# 03_-_28PINS_SCHEMATIC.net
KiCad netlist of a schematic drawn in Altium Designer
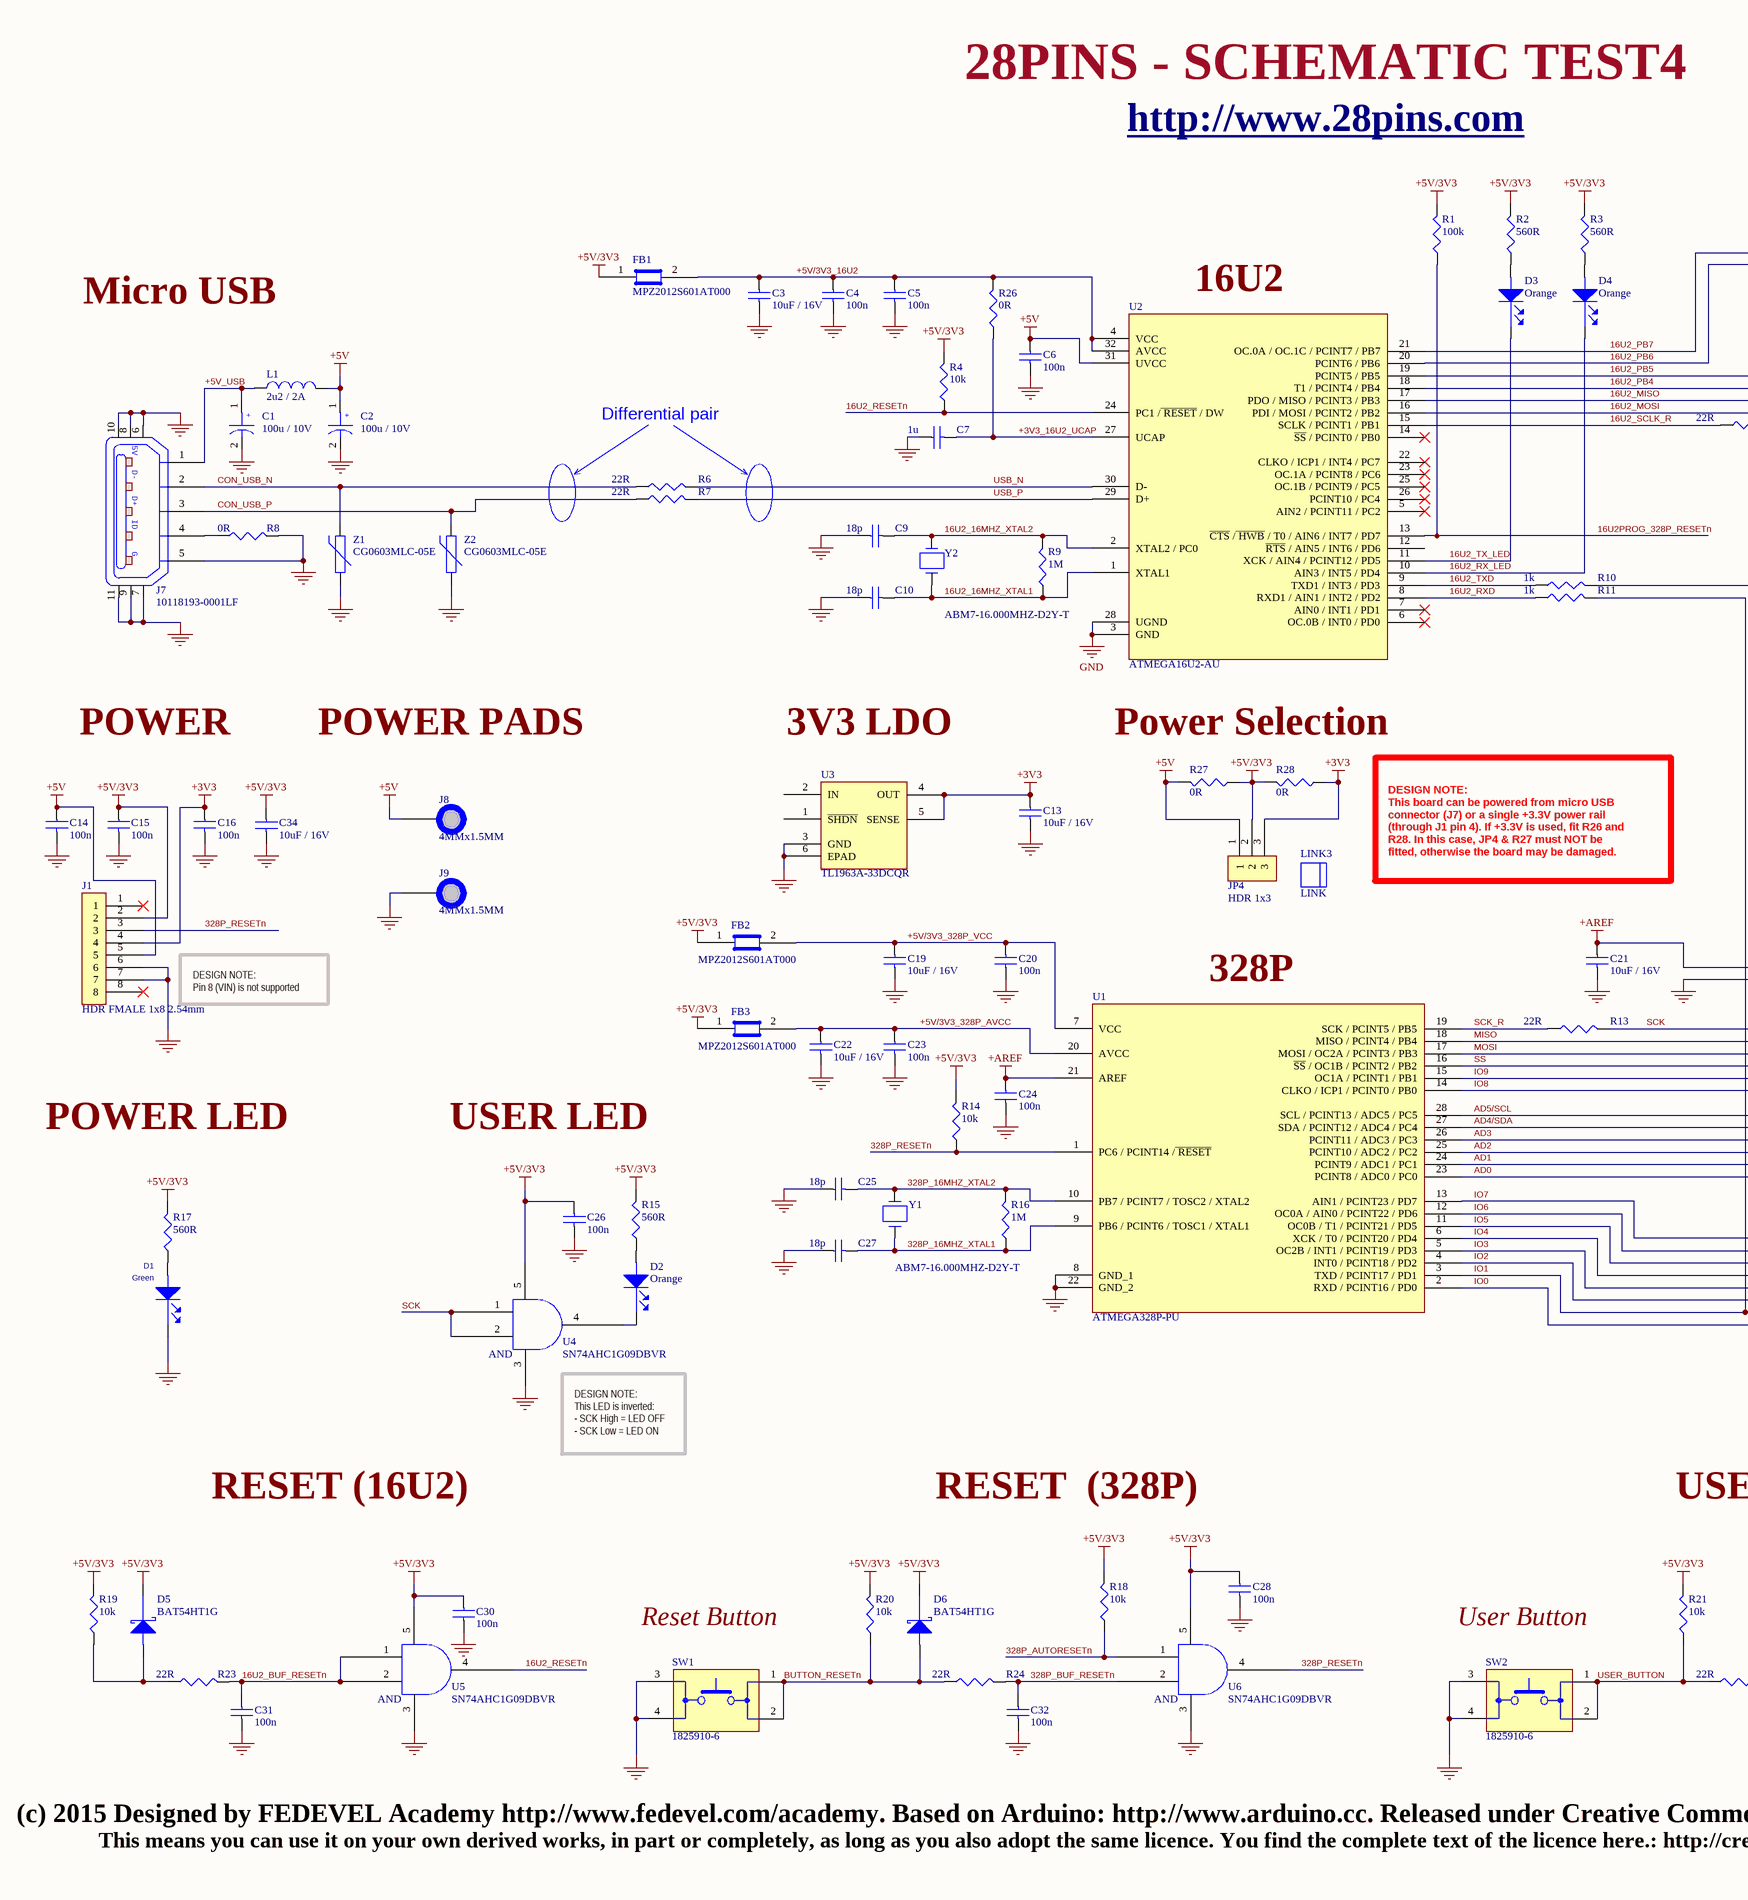
[diagram p0: [03] - 28PINS SCHEMATIC.SchDoc, left]
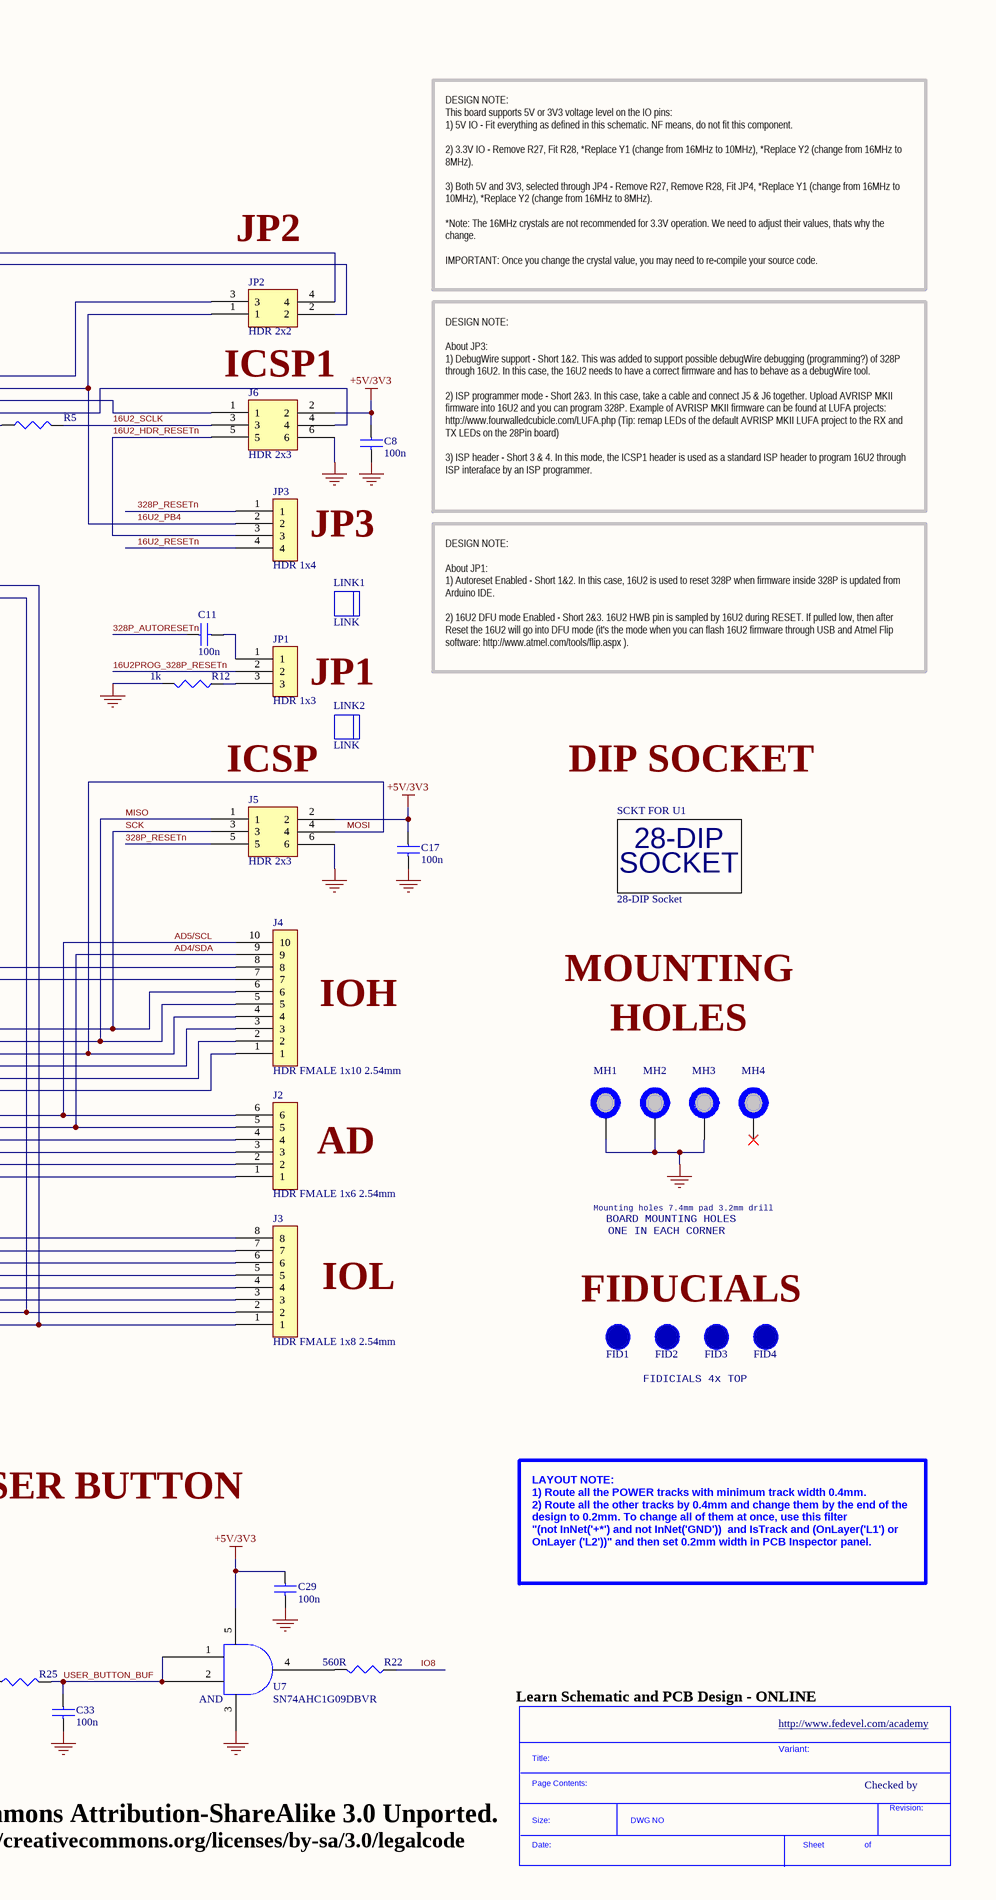
[diagram p1: [03] - 28PINS SCHEMATIC.SchDoc, right]

(export (version "E")
  (design (tool "Eeschema 10.0.6"))
  (components
    (comp (ref "*") (value "SDTitleBlock") (libsource (lib "*") (part "SDTitleBlock")))
    (comp (ref "C1")
      (value "100u / 10V")
      (footprint "C_ALU_C_SIZE")
      (description "CAP ALUM 100UF 10V 20% SMD")
      (fields
        (field (name "MANUFACTURER") "Panasonic Electronic Components")
        (field (name "MANUFACTURER PART NUMBER") "EEE-1AA101WR")
        (field (name ".CREATOR") "MM")
        (field (name ".CHECKED PCB") "RF")
        (field (name ".CHECKED SCH") "RF")
      )
      (libsource (lib "Integrated_Library_FEDEVEL_APR_2015") (part "EEE-1AA101WR"))
    )
    (comp (ref "C2")
      (value "100u / 10V")
      (footprint "C_ALU_C_SIZE")
      (description "CAP ALUM 100UF 10V 20% SMD")
      (fields
        (field (name "MANUFACTURER") "Panasonic Electronic Components")
        (field (name "MANUFACTURER PART NUMBER") "EEE-1AA101WR")
        (field (name ".CREATOR") "MM")
        (field (name ".CHECKED PCB") "RF")
        (field (name ".CHECKED SCH") "RF")
      )
      (libsource (lib "Integrated_Library_FEDEVEL_APR_2015") (part "EEE-1AA101WR"))
    )
    (comp (ref "C3")
      (value "10uF / 16V")
      (footprint "C0805")
      (description "CAP CER 10UF 16V 20% X5R 0805")
      (fields
        (field (name "MANUFACTURER") "TDK Corporation")
        (field (name "MANUFACTURER PART NUMBER") "C2012X5R1C106M/1.25")
      )
      (libsource (lib "Integrated_Library_FEDEVEL_APR_2015") (part "C2012X5R1C106M"))
    )
    (comp (ref "C4")
      (value "100n")
      (footprint "C0805")
      (description "CAP CER 0.1UF 50V 10% X7R 0805")
      (fields
        (field (name "MANUFACTURER") "TDK Corporation")
        (field (name "MANUFACTURER PART NUMBER") "C2012X7R1H104K085AA")
        (field (name ".CREATOR") "MM")
        (field (name ".CHECKED PCB") "RF")
        (field (name ".CHECKED SCH") "RF")
      )
      (libsource (lib "Integrated_Library_FEDEVEL_APR_2015") (part "C2012X7R1H104K085AA"))
    )
    (comp (ref "C5")
      (value "100n")
      (footprint "C0805")
      (description "CAP CER 0.1UF 50V 10% X7R 0805")
      (fields
        (field (name "MANUFACTURER") "TDK Corporation")
        (field (name "MANUFACTURER PART NUMBER") "C2012X7R1H104K085AA")
        (field (name ".CREATOR") "MM")
        (field (name ".CHECKED PCB") "RF")
        (field (name ".CHECKED SCH") "RF")
      )
      (libsource (lib "Integrated_Library_FEDEVEL_APR_2015") (part "C2012X7R1H104K085AA"))
    )
    (comp (ref "C6")
      (value "100n")
      (footprint "C0805")
      (description "CAP CER 0.1UF 50V 10% X7R 0805")
      (fields
        (field (name "MANUFACTURER") "TDK Corporation")
        (field (name "MANUFACTURER PART NUMBER") "C2012X7R1H104K085AA")
        (field (name ".CREATOR") "MM")
        (field (name ".CHECKED PCB") "RF")
        (field (name ".CHECKED SCH") "RF")
      )
      (libsource (lib "Integrated_Library_FEDEVEL_APR_2015") (part "C2012X7R1H104K085AA"))
    )
    (comp (ref "C7")
      (value "1u")
      (footprint "C0805")
      (description "CAP CER 1UF 25V 10% X5R 0805")
      (fields
        (field (name "MANUFACTURER") "TDK Corporation")
        (field (name "MANUFACTURER PART NUMBER") "C2012X5R1E105K125AA")
        (field (name ".CREATOR") "MM")
        (field (name ".CHECKED PCB") "RF")
        (field (name ".CHECKED SCH") "RF")
      )
      (libsource (lib "Integrated_Library_FEDEVEL_APR_2015") (part "C2012X5R1E105K125AA"))
    )
    (comp (ref "C8")
      (value "100n")
      (footprint "C0805")
      (description "CAP CER 0.1UF 50V 10% X7R 0805")
      (fields
        (field (name "MANUFACTURER") "TDK Corporation")
        (field (name "MANUFACTURER PART NUMBER") "C2012X7R1H104K085AA")
        (field (name ".CREATOR") "MM")
        (field (name ".CHECKED PCB") "RF")
        (field (name ".CHECKED SCH") "RF")
      )
      (libsource (lib "Integrated_Library_FEDEVEL_APR_2015") (part "C2012X7R1H104K085AA"))
    )
    (comp (ref "C9")
      (value "18p")
      (footprint "C0805")
      (description "CAP CER 18PF 50V 5% NP0 0805")
      (fields
        (field (name "MANUFACTURER") "Kemet")
        (field (name "MANUFACTURER PART NUMBER") "C0805C180J5GACTU")
        (field (name ".CREATOR") "MM")
        (field (name ".CHECKED PCB") "RF")
        (field (name ".CHECKED SCH") "RF")
      )
      (libsource (lib "Integrated_Library_FEDEVEL_APR_2015") (part "C0805C180J5GACTU"))
    )
    (comp (ref "C10")
      (value "18p")
      (footprint "C0805")
      (description "CAP CER 18PF 50V 5% NP0 0805")
      (fields
        (field (name "MANUFACTURER") "Kemet")
        (field (name "MANUFACTURER PART NUMBER") "C0805C180J5GACTU")
        (field (name ".CREATOR") "MM")
        (field (name ".CHECKED PCB") "RF")
        (field (name ".CHECKED SCH") "RF")
      )
      (libsource (lib "Integrated_Library_FEDEVEL_APR_2015") (part "C0805C180J5GACTU"))
    )
    (comp (ref "C11")
      (value "100n")
      (footprint "C0805")
      (description "CAP CER 0.1UF 50V 10% X7R 0805")
      (fields
        (field (name "MANUFACTURER") "TDK Corporation")
        (field (name "MANUFACTURER PART NUMBER") "C2012X7R1H104K085AA")
        (field (name ".CREATOR") "MM")
        (field (name ".CHECKED PCB") "RF")
        (field (name ".CHECKED SCH") "RF")
      )
      (libsource (lib "Integrated_Library_FEDEVEL_APR_2015") (part "C2012X7R1H104K085AA"))
    )
    (comp (ref "C13")
      (value "10uF / 16V")
      (footprint "C0805")
      (description "CAP CER 10UF 16V 20% X5R 0805")
      (fields
        (field (name "MANUFACTURER") "TDK Corporation")
        (field (name "MANUFACTURER PART NUMBER") "C2012X5R1C106M/1.25")
      )
      (libsource (lib "Integrated_Library_FEDEVEL_APR_2015") (part "C2012X5R1C106M"))
    )
    (comp (ref "C14")
      (value "100n")
      (footprint "C0805")
      (description "CAP CER 0.1UF 50V 10% X7R 0805")
      (fields
        (field (name "MANUFACTURER") "TDK Corporation")
        (field (name "MANUFACTURER PART NUMBER") "C2012X7R1H104K085AA")
        (field (name ".CREATOR") "MM")
        (field (name ".CHECKED PCB") "RF")
        (field (name ".CHECKED SCH") "RF")
      )
      (libsource (lib "Integrated_Library_FEDEVEL_APR_2015") (part "C2012X7R1H104K085AA"))
    )
    (comp (ref "C15")
      (value "100n")
      (footprint "C0805")
      (description "CAP CER 0.1UF 50V 10% X7R 0805")
      (fields
        (field (name "MANUFACTURER") "TDK Corporation")
        (field (name "MANUFACTURER PART NUMBER") "C2012X7R1H104K085AA")
        (field (name ".CREATOR") "MM")
        (field (name ".CHECKED PCB") "RF")
        (field (name ".CHECKED SCH") "RF")
      )
      (libsource (lib "Integrated_Library_FEDEVEL_APR_2015") (part "C2012X7R1H104K085AA"))
    )
    (comp (ref "C16")
      (value "100n")
      (footprint "C0805")
      (description "CAP CER 0.1UF 50V 10% X7R 0805")
      (fields
        (field (name "MANUFACTURER") "TDK Corporation")
        (field (name "MANUFACTURER PART NUMBER") "C2012X7R1H104K085AA")
        (field (name ".CREATOR") "MM")
        (field (name ".CHECKED PCB") "RF")
        (field (name ".CHECKED SCH") "RF")
      )
      (libsource (lib "Integrated_Library_FEDEVEL_APR_2015") (part "C2012X7R1H104K085AA"))
    )
    (comp (ref "C17")
      (value "100n")
      (footprint "C0805")
      (description "CAP CER 0.1UF 50V 10% X7R 0805")
      (fields
        (field (name "MANUFACTURER") "TDK Corporation")
        (field (name "MANUFACTURER PART NUMBER") "C2012X7R1H104K085AA")
        (field (name ".CREATOR") "MM")
        (field (name ".CHECKED PCB") "RF")
        (field (name ".CHECKED SCH") "RF")
      )
      (libsource (lib "Integrated_Library_FEDEVEL_APR_2015") (part "C2012X7R1H104K085AA"))
    )
    (comp (ref "C19")
      (value "10uF / 16V")
      (footprint "C0805")
      (description "CAP CER 10UF 16V 20% X5R 0805")
      (fields
        (field (name "MANUFACTURER") "TDK Corporation")
        (field (name "MANUFACTURER PART NUMBER") "C2012X5R1C106M/1.25")
      )
      (libsource (lib "Integrated_Library_FEDEVEL_APR_2015") (part "C2012X5R1C106M"))
    )
    (comp (ref "C20")
      (value "100n")
      (footprint "C0805")
      (description "CAP CER 0.1UF 50V 10% X7R 0805")
      (fields
        (field (name "MANUFACTURER") "TDK Corporation")
        (field (name "MANUFACTURER PART NUMBER") "C2012X7R1H104K085AA")
        (field (name ".CREATOR") "MM")
        (field (name ".CHECKED PCB") "RF")
        (field (name ".CHECKED SCH") "RF")
      )
      (libsource (lib "Integrated_Library_FEDEVEL_APR_2015") (part "C2012X7R1H104K085AA"))
    )
    (comp (ref "C21")
      (value "10uF / 16V")
      (footprint "C0805")
      (description "CAP CER 10UF 16V 20% X5R 0805")
      (fields
        (field (name "MANUFACTURER") "TDK Corporation")
        (field (name "MANUFACTURER PART NUMBER") "C2012X5R1C106M/1.25")
      )
      (libsource (lib "Integrated_Library_FEDEVEL_APR_2015") (part "C2012X5R1C106M"))
    )
    (comp (ref "C22")
      (value "10uF / 16V")
      (footprint "C0805")
      (description "CAP CER 10UF 16V 20% X5R 0805")
      (fields
        (field (name "MANUFACTURER") "TDK Corporation")
        (field (name "MANUFACTURER PART NUMBER") "C2012X5R1C106M/1.25")
      )
      (libsource (lib "Integrated_Library_FEDEVEL_APR_2015") (part "C2012X5R1C106M"))
    )
    (comp (ref "C23")
      (value "100n")
      (footprint "C0805")
      (description "CAP CER 0.1UF 50V 10% X7R 0805")
      (fields
        (field (name "MANUFACTURER") "TDK Corporation")
        (field (name "MANUFACTURER PART NUMBER") "C2012X7R1H104K085AA")
        (field (name ".CREATOR") "MM")
        (field (name ".CHECKED PCB") "RF")
        (field (name ".CHECKED SCH") "RF")
      )
      (libsource (lib "Integrated_Library_FEDEVEL_APR_2015") (part "C2012X7R1H104K085AA"))
    )
    (comp (ref "C24")
      (value "100n")
      (footprint "C0805")
      (description "CAP CER 0.1UF 50V 10% X7R 0805")
      (fields
        (field (name "MANUFACTURER") "TDK Corporation")
        (field (name "MANUFACTURER PART NUMBER") "C2012X7R1H104K085AA")
        (field (name ".CREATOR") "MM")
        (field (name ".CHECKED PCB") "RF")
        (field (name ".CHECKED SCH") "RF")
      )
      (libsource (lib "Integrated_Library_FEDEVEL_APR_2015") (part "C2012X7R1H104K085AA"))
    )
    (comp (ref "C25")
      (value "18p")
      (footprint "C0805")
      (description "CAP CER 18PF 50V 5% NP0 0805")
      (fields
        (field (name "MANUFACTURER") "Kemet")
        (field (name "MANUFACTURER PART NUMBER") "C0805C180J5GACTU")
        (field (name ".CREATOR") "MM")
        (field (name ".CHECKED PCB") "RF")
        (field (name ".CHECKED SCH") "RF")
      )
      (libsource (lib "Integrated_Library_FEDEVEL_APR_2015") (part "C0805C180J5GACTU"))
    )
    (comp (ref "C26")
      (value "100n")
      (footprint "C0805")
      (description "CAP CER 0.1UF 50V 10% X7R 0805")
      (fields
        (field (name "MANUFACTURER") "TDK Corporation")
        (field (name "MANUFACTURER PART NUMBER") "C2012X7R1H104K085AA")
        (field (name ".CREATOR") "MM")
        (field (name ".CHECKED PCB") "RF")
        (field (name ".CHECKED SCH") "RF")
      )
      (libsource (lib "Integrated_Library_FEDEVEL_APR_2015") (part "C2012X7R1H104K085AA"))
    )
    (comp (ref "C27")
      (value "18p")
      (footprint "C0805")
      (description "CAP CER 18PF 50V 5% NP0 0805")
      (fields
        (field (name "MANUFACTURER") "Kemet")
        (field (name "MANUFACTURER PART NUMBER") "C0805C180J5GACTU")
        (field (name ".CREATOR") "MM")
        (field (name ".CHECKED PCB") "RF")
        (field (name ".CHECKED SCH") "RF")
      )
      (libsource (lib "Integrated_Library_FEDEVEL_APR_2015") (part "C0805C180J5GACTU"))
    )
    (comp (ref "C28")
      (value "100n")
      (footprint "C0805")
      (description "CAP CER 0.1UF 50V 10% X7R 0805")
      (fields
        (field (name "MANUFACTURER") "TDK Corporation")
        (field (name "MANUFACTURER PART NUMBER") "C2012X7R1H104K085AA")
        (field (name ".CREATOR") "MM")
        (field (name ".CHECKED PCB") "RF")
        (field (name ".CHECKED SCH") "RF")
      )
      (libsource (lib "Integrated_Library_FEDEVEL_APR_2015") (part "C2012X7R1H104K085AA"))
    )
    (comp (ref "C29")
      (value "100n")
      (footprint "C0805")
      (description "CAP CER 0.1UF 50V 10% X7R 0805")
      (fields
        (field (name "MANUFACTURER") "TDK Corporation")
        (field (name "MANUFACTURER PART NUMBER") "C2012X7R1H104K085AA")
        (field (name ".CREATOR") "MM")
        (field (name ".CHECKED PCB") "RF")
        (field (name ".CHECKED SCH") "RF")
      )
      (libsource (lib "Integrated_Library_FEDEVEL_APR_2015") (part "C2012X7R1H104K085AA"))
    )
    (comp (ref "C30")
      (value "100n")
      (footprint "C0805")
      (description "CAP CER 0.1UF 50V 10% X7R 0805")
      (fields
        (field (name "MANUFACTURER") "TDK Corporation")
        (field (name "MANUFACTURER PART NUMBER") "C2012X7R1H104K085AA")
        (field (name ".CREATOR") "MM")
        (field (name ".CHECKED PCB") "RF")
        (field (name ".CHECKED SCH") "RF")
      )
      (libsource (lib "Integrated_Library_FEDEVEL_APR_2015") (part "C2012X7R1H104K085AA"))
    )
    (comp (ref "C31")
      (value "100n")
      (footprint "C0805")
      (description "CAP CER 0.1UF 50V 10% X7R 0805")
      (fields
        (field (name "MANUFACTURER") "TDK Corporation")
        (field (name "MANUFACTURER PART NUMBER") "C2012X7R1H104K085AA")
        (field (name ".CREATOR") "MM")
        (field (name ".CHECKED PCB") "RF")
        (field (name ".CHECKED SCH") "RF")
      )
      (libsource (lib "Integrated_Library_FEDEVEL_APR_2015") (part "C2012X7R1H104K085AA"))
    )
    (comp (ref "C32")
      (value "100n")
      (footprint "C0805")
      (description "CAP CER 0.1UF 50V 10% X7R 0805")
      (fields
        (field (name "MANUFACTURER") "TDK Corporation")
        (field (name "MANUFACTURER PART NUMBER") "C2012X7R1H104K085AA")
        (field (name ".CREATOR") "MM")
        (field (name ".CHECKED PCB") "RF")
        (field (name ".CHECKED SCH") "RF")
      )
      (libsource (lib "Integrated_Library_FEDEVEL_APR_2015") (part "C2012X7R1H104K085AA"))
    )
    (comp (ref "C33")
      (value "100n")
      (footprint "C0805")
      (description "CAP CER 0.1UF 50V 10% X7R 0805")
      (fields
        (field (name "MANUFACTURER") "TDK Corporation")
        (field (name "MANUFACTURER PART NUMBER") "C2012X7R1H104K085AA")
        (field (name ".CREATOR") "MM")
        (field (name ".CHECKED PCB") "RF")
        (field (name ".CHECKED SCH") "RF")
      )
      (libsource (lib "Integrated_Library_FEDEVEL_APR_2015") (part "C2012X7R1H104K085AA"))
    )
    (comp (ref "C34")
      (value "10uF / 16V")
      (footprint "C0805")
      (description "CAP CER 10UF 16V 20% X5R 0805")
      (fields
        (field (name "MANUFACTURER") "TDK Corporation")
        (field (name "MANUFACTURER PART NUMBER") "C2012X5R1C106M/1.25")
      )
      (libsource (lib "Integrated_Library_FEDEVEL_APR_2015") (part "C2012X5R1C106M"))
    )
    (comp (ref "D1")
      (value "Green")
      (footprint "LED_0603")
      (description "LED SMARTLED GREEN 570NM 0603")
      (fields
        (field (name "MANUFACTURER") "OSRAM Opto Semiconductors Inc")
        (field (name "MANUFACTURER PART NUMBER") "LG L29K-G2J1-24-Z")
      )
      (libsource (lib "Integrated_Library_FEDEVEL_APR_2015") (part "LG L29K-G2J1-24-Z"))
    )
    (comp (ref "D2")
      (value "Orange")
      (footprint "LED_0603")
      (description "LED SMARTLED ORANGE 606NM 0603")
      (fields
        (field (name "MANUFACTURER") "OSRAM Opto Semiconductors Inc")
        (field (name "MANUFACTURER PART NUMBER") "LO L29K-H2K1-24-Z")
      )
      (libsource (lib "Integrated_Library_FEDEVEL_APR_2015") (part "LO L29K-H2K1-24-Z"))
    )
    (comp (ref "D3")
      (value "Orange")
      (footprint "LED_0603")
      (description "LED SMARTLED ORANGE 606NM 0603")
      (fields
        (field (name "MANUFACTURER") "OSRAM Opto Semiconductors Inc")
        (field (name "MANUFACTURER PART NUMBER") "LO L29K-H2K1-24-Z")
      )
      (libsource (lib "Integrated_Library_FEDEVEL_APR_2015") (part "LO L29K-H2K1-24-Z"))
    )
    (comp (ref "D4")
      (value "Orange")
      (footprint "LED_0603")
      (description "LED SMARTLED ORANGE 606NM 0603")
      (fields
        (field (name "MANUFACTURER") "OSRAM Opto Semiconductors Inc")
        (field (name "MANUFACTURER PART NUMBER") "LO L29K-H2K1-24-Z")
      )
      (libsource (lib "Integrated_Library_FEDEVEL_APR_2015") (part "LO L29K-H2K1-24-Z"))
    )
    (comp (ref "D5")
      (value "BAT54HT1G")
      (footprint "SOD323")
      (description "DIODE SCHOTTKY 30V 0.2A SOD323")
      (fields (field (name "MANUFACTURER") "Fairchild Semiconductor") (field (name ".CREATOR") "MM"))
      (libsource (lib "Integrated_Library_FEDEVEL_APR_2015") (part "BAT54HT1G"))
    )
    (comp (ref "D6")
      (value "BAT54HT1G")
      (footprint "SOD323")
      (description "DIODE SCHOTTKY 30V 0.2A SOD323")
      (fields (field (name "MANUFACTURER") "Fairchild Semiconductor") (field (name ".CREATOR") "MM"))
      (libsource (lib "Integrated_Library_FEDEVEL_APR_2015") (part "BAT54HT1G"))
    )
    (comp (ref "FB1")
      (value "MPZ2012S601AT000")
      (footprint "C0805")
      (description "FERRITE CHIP BEAD 600 OHM SMD")
      (fields
        (field (name "MANUFACTURER") "TDK Corporation")
        (field (name ".CREATOR") "MM")
        (field (name ".CHECKED PCB") "RF")
        (field (name ".CHECKED SCH") "RF")
      )
      (libsource (lib "Integrated_Library_FEDEVEL_APR_2015") (part "MPZ2012S601AT000"))
    )
    (comp (ref "FB2")
      (value "MPZ2012S601AT000")
      (footprint "C0805")
      (description "FERRITE CHIP BEAD 600 OHM SMD")
      (fields
        (field (name "MANUFACTURER") "TDK Corporation")
        (field (name ".CREATOR") "MM")
        (field (name ".CHECKED PCB") "RF")
        (field (name ".CHECKED SCH") "RF")
      )
      (libsource (lib "Integrated_Library_FEDEVEL_APR_2015") (part "MPZ2012S601AT000"))
    )
    (comp (ref "FB3")
      (value "MPZ2012S601AT000")
      (footprint "C0805")
      (description "FERRITE CHIP BEAD 600 OHM SMD")
      (fields
        (field (name "MANUFACTURER") "TDK Corporation")
        (field (name ".CREATOR") "MM")
        (field (name ".CHECKED PCB") "RF")
        (field (name ".CHECKED SCH") "RF")
      )
      (libsource (lib "Integrated_Library_FEDEVEL_APR_2015") (part "MPZ2012S601AT000"))
    )
    (comp (ref "FID1")
      (value "FID_1MMC")
      (footprint "FID_40X120D")
      (description "Fiducial 40mil Diameter, 120mil Mask")
      (libsource (lib "Integrated_Library_FEDEVEL_APR_2015") (part "FID_1MMC"))
    )
    (comp (ref "FID2")
      (value "FID_1MMC")
      (footprint "FID_40X120D")
      (description "Fiducial 40mil Diameter, 120mil Mask")
      (libsource (lib "Integrated_Library_FEDEVEL_APR_2015") (part "FID_1MMC"))
    )
    (comp (ref "FID3")
      (value "FID_1MMC")
      (footprint "FID_40X120D")
      (description "Fiducial 40mil Diameter, 120mil Mask")
      (libsource (lib "Integrated_Library_FEDEVEL_APR_2015") (part "FID_1MMC"))
    )
    (comp (ref "FID4")
      (value "FID_1MMC")
      (footprint "FID_40X120D")
      (description "Fiducial 40mil Diameter, 120mil Mask")
      (libsource (lib "Integrated_Library_FEDEVEL_APR_2015") (part "FID_1MMC"))
    )
    (comp (ref "J1")
      (value "HDR FMALE 1x8 2.54mm")
      (footprint "Hdr_Female_1x8_2.54mm")
      (description "08-WAY SIL VERT SOCKET L/FREE")
      (fields
        (field (name "MANUFACTURER") "Harwin Inc")
        (field (name "MANUFACTURER PART NUMBER") "M20-7820842")
        (field (name ".CREATOR") "MM")
        (field (name ".CHECKED PCB") "RF")
        (field (name ".CHECKED SCH") "RF")
      )
      (libsource (lib "") (part "M20-7820842_1"))
    )
    (comp (ref "J2")
      (value "HDR FMALE 1x6 2.54mm")
      (footprint "Hdr_Female_1x6_2.54mm")
      (description "06-WAY SIL VERT SOCKET L/FREE")
      (fields
        (field (name "MANUFACTURER") "Harwin Inc")
        (field (name "MANUFACTURER PART NUMBER") "M20-7820646")
        (field (name ".CHECKED PCB") "MM")
        (field (name ".CHECKED SCH") "MM")
        (field (name ".CREATOR") "MM")
      )
      (libsource (lib "Integrated_Library_FEDEVEL_APR_2015") (part "M20-7820646"))
    )
    (comp (ref "J3")
      (value "HDR FMALE 1x8 2.54mm")
      (footprint "Hdr_Female_1x8_2.54mm")
      (description "08-WAY SIL VERT SOCKET L/FREE")
      (fields
        (field (name "MANUFACTURER") "Harwin Inc")
        (field (name "MANUFACTURER PART NUMBER") "M20-7820842")
        (field (name ".CREATOR") "MM")
        (field (name ".CHECKED PCB") "RF")
        (field (name ".CHECKED SCH") "RF")
      )
      (libsource (lib "Integrated_Library_FEDEVEL_APR_2015") (part "M20-7820842"))
    )
    (comp (ref "J4")
      (value "HDR FMALE 1x10 2.54mm")
      (footprint "Hdr_Female_1x10_2.54mm")
      (description "10-WAY SIL VERT SOCKET L/FREE")
      (fields
        (field (name "MANUFACTURER") "Harwin Inc")
        (field (name "MANUFACTURER PART NUMBER") "M20-7821046")
        (field (name ".CREATOR") "MM")
        (field (name ".CHECKED PCB") "RF")
        (field (name ".CHECKED SCH") "RF")
      )
      (libsource (lib "Integrated_Library_FEDEVEL_APR_2015") (part "M20-7821046"))
    )
    (comp (ref "J5")
      (value "HDR 2x3")
      (footprint "HDR_2x3_2.54MM")
      (description "CONN HEADER 6POS .100 STR 30AU")
      (fields
        (field (name "MANUFACTURER") "FCI")
        (field (name "MANUFACTURER PART NUMBER") "67997-106HLF")
        (field (name ".CREATOR") "MM")
        (field (name ".CHECKED PCB") "RF")
        (field (name ".CHECKED SCH") "RF")
      )
      (libsource (lib "Integrated_Library_FEDEVEL_APR_2015") (part "67997-106HLF"))
    )
    (comp (ref "J6")
      (value "HDR 2x3")
      (footprint "HDR_2x3_2.54MM")
      (description "CONN HEADER 6POS .100 STR 30AU")
      (fields
        (field (name "MANUFACTURER") "FCI")
        (field (name "MANUFACTURER PART NUMBER") "67997-106HLF")
        (field (name ".CREATOR") "MM")
        (field (name ".CHECKED PCB") "RF")
        (field (name ".CHECKED SCH") "RF")
      )
      (libsource (lib "Integrated_Library_FEDEVEL_APR_2015") (part "67997-106HLF"))
    )
    (comp (ref "J7")
      (value "10118193-0001LF")
      (footprint "10118193")
      (description "CONN USB MICRO B RECPT SMT R/A")
      (fields
        (field (name "MANUFACTURER") "FCI")
        (field (name ".CREATOR") "MM")
        (field (name ".CHECKED PCB") "RF")
        (field (name ".CHECKED SCH") "MM")
      )
      (libsource (lib "Integrated_Library_FEDEVEL_APR_2015") (part "10118193-0001LF"))
    )
    (comp (ref "J8")
      (value "4MMx1.5MM")
      (footprint "PAD_WITH_HOLE_4MMx1.5MM")
      (description "Pad with a hole 4mm x 1.5mm")
      (libsource (lib "Integrated_Library_FEDEVEL_APR_2015") (part "PAD_WITH_HOLE_4MMx1.5MM"))
    )
    (comp (ref "J9")
      (value "4MMx1.5MM")
      (footprint "PAD_WITH_HOLE_4MMx1.5MM")
      (description "Pad with a hole 4mm x 1.5mm")
      (libsource (lib "Integrated_Library_FEDEVEL_APR_2015") (part "PAD_WITH_HOLE_4MMx1.5MM"))
    )
    (comp (ref "JP1")
      (value "HDR 1x3")
      (footprint "Hdr_1x3_2.54mm")
      (description "BERGSTIK II .100\" SR STRAIGHT")
      (fields
        (field (name "MANUFACTURER") "FCI")
        (field (name "MANUFACTURER PART NUMBER") "68000-103HLF")
        (field (name ".CREATOR") "MM")
      )
      (libsource (lib "") (part "68000-103HLF_1"))
    )
    (comp (ref "JP2")
      (value "HDR 2x2")
      (footprint "HDR_2x2_2.54MM")
      (description "CONN HEADER 4POS .100 STR 15AU")
      (fields
        (field (name "MANUFACTURER") "FCI")
        (field (name "MANUFACTURER PART NUMBER") "68602-204HLF")
        (field (name ".CREATOR") "MM")
        (field (name ".CHECKED PCB") "RF")
        (field (name ".CHECKED SCH") "RF")
      )
      (libsource (lib "Integrated_Library_FEDEVEL_APR_2015") (part "68602-204HLF"))
    )
    (comp (ref "JP3")
      (value "HDR 1x4")
      (footprint "HDR_1x4_2.54MM")
      (description "CONN HEADER 4POS .100 STR 15AU")
      (fields
        (field (name "MANUFACTURER") "FCI")
        (field (name "MANUFACTURER PART NUMBER") "68001-204HLF")
        (field (name ".CHECKED PCB") "RF")
        (field (name ".CHECKED SCH") "RF")
      )
      (libsource (lib "Integrated_Library_FEDEVEL_APR_2015") (part "68001-204HLF"))
    )
    (comp (ref "JP4")
      (value "HDR 1x3")
      (footprint "Hdr_1x3_2.54mm")
      (description "BERGSTIK II .100\" SR STRAIGHT")
      (fields
        (field (name "MANUFACTURER") "FCI")
        (field (name "MANUFACTURER PART NUMBER") "68000-103HLF")
        (field (name ".CREATOR") "MM")
      )
      (libsource (lib "Integrated_Library_FEDEVEL_APR_2015") (part "68000-103HLF"))
    )
    (comp (ref "L1")
      (value "2u2 / 2A")
      (footprint "C1210_IND")
      (description "FIXED IND 2.2UH 2A 80 MOHM SMD")
      (fields
        (field (name "MANUFACTURER") "Kemet")
        (field (name "MANUFACTURER PART NUMBER") "L1210R2R2MDWIT")
        (field (name ".CREATOR") "MM")
        (field (name ".CHECKED PCB") "RF")
        (field (name ".CHECKED SCH") "RF")
      )
      (libsource (lib "Integrated_Library_FEDEVEL_APR_2015") (part "L1210R2R2MDWIT"))
    )
    (comp (ref "LINK1")
      (value "LINK")
      (description "CONN JUMPER SHORTING .100\" GOLD")
      (fields
        (field (name "MANUFACTURER") "Sullins Connector Solutions")
        (field (name "MANUFACTURER PART NUMBER") "QPC02SXGN-RC")
      )
      (libsource (lib "Integrated_Library_FEDEVEL_APR_2015") (part "QPC02SXGN-RC"))
    )
    (comp (ref "LINK2")
      (value "LINK")
      (description "CONN JUMPER SHORTING .100\" GOLD")
      (fields
        (field (name "MANUFACTURER") "Sullins Connector Solutions")
        (field (name "MANUFACTURER PART NUMBER") "QPC02SXGN-RC")
      )
      (libsource (lib "Integrated_Library_FEDEVEL_APR_2015") (part "QPC02SXGN-RC"))
    )
    (comp (ref "LINK3")
      (value "LINK")
      (description "CONN JUMPER SHORTING .100\" GOLD")
      (fields
        (field (name "MANUFACTURER") "Sullins Connector Solutions")
        (field (name "MANUFACTURER PART NUMBER") "QPC02SXGN-RC")
      )
      (libsource (lib "Integrated_Library_FEDEVEL_APR_2015") (part "QPC02SXGN-RC"))
    )
    (comp (ref "MH1")
      (value "MH_7.4MMC_3.2MMD")
      (footprint "MH_7.4MMD_3.2MMD")
      (description "Mounting Hole 7.4mm Diameter, 3.2mm Drill")
      (fields (field (name ".CREATOR") "MM"))
      (libsource (lib "Integrated_Library_FEDEVEL_APR_2015") (part "MH_7.4MMC_3.2MMD"))
    )
    (comp (ref "MH2")
      (value "MH_7.4MMC_3.2MMD")
      (footprint "MH_7.4MMD_3.2MMD")
      (description "Mounting Hole 7.4mm Diameter, 3.2mm Drill")
      (fields (field (name ".CREATOR") "MM"))
      (libsource (lib "Integrated_Library_FEDEVEL_APR_2015") (part "MH_7.4MMC_3.2MMD"))
    )
    (comp (ref "MH3")
      (value "MH_7.4MMC_3.2MMD")
      (footprint "MH_7.4MMD_3.2MMD")
      (description "Mounting Hole 7.4mm Diameter, 3.2mm Drill")
      (fields (field (name ".CREATOR") "MM"))
      (libsource (lib "Integrated_Library_FEDEVEL_APR_2015") (part "MH_7.4MMC_3.2MMD"))
    )
    (comp (ref "MH4")
      (value "MH_7.4MMNC_3.2MMD")
      (footprint "MH_7.4MMD_3.2MMD_NON_COPPER_NPTH")
      (description "Mounting Hole 7.4mm Diameter (Non Copper), 3.2mm Drill NPTH")
      (libsource (lib "Integrated_Library_FEDEVEL_APR_2015") (part "MH_7.4MMNC_3.2MMD"))
    )
    (comp (ref "R1")
      (value "100k")
      (footprint "R0805")
      (description "RES SMD 100K OHM 1% 1/8W 0805")
      (fields
        (field (name "MANUFACTURER") "Yageo")
        (field (name "MANUFACTURER PART NUMBER") "RC0805FR-07100KL")
        (field (name ".CREATOR") "MM")
        (field (name ".CHECKED PCB") "RF")
        (field (name ".CHECKED SCH") "RF")
      )
      (libsource (lib "Integrated_Library_FEDEVEL_APR_2015") (part "RC0805FR-07100KL"))
    )
    (comp (ref "R2")
      (value "560R")
      (footprint "R0805")
      (description "RES SMD 560 OHM 1% 1/8W 0805")
      (fields
        (field (name "MANUFACTURER") "Yageo")
        (field (name "MANUFACTURER PART NUMBER") "RC0805FR-07560RL")
        (field (name ".CREATOR") "MM")
        (field (name ".CHECKED PCB") "RF")
        (field (name ".CHECKED SCH") "RF")
      )
      (libsource (lib "Integrated_Library_FEDEVEL_APR_2015") (part "RC0805FR-07560RL"))
    )
    (comp (ref "R3")
      (value "560R")
      (footprint "R0805")
      (description "RES SMD 560 OHM 1% 1/8W 0805")
      (fields
        (field (name "MANUFACTURER") "Yageo")
        (field (name "MANUFACTURER PART NUMBER") "RC0805FR-07560RL")
        (field (name ".CREATOR") "MM")
        (field (name ".CHECKED PCB") "RF")
        (field (name ".CHECKED SCH") "RF")
      )
      (libsource (lib "Integrated_Library_FEDEVEL_APR_2015") (part "RC0805FR-07560RL"))
    )
    (comp (ref "R4")
      (value "10k")
      (footprint "R0805")
      (description "RES SMD 10K OHM 1% 1/8W 0805")
      (fields
        (field (name "MANUFACTURER") "Yageo")
        (field (name "MANUFACTURER PART NUMBER") "RC0805FR-0710KL")
        (field (name ".CREATOR") "MM")
        (field (name ".CHECKED PCB") "RF")
        (field (name ".CHECKED SCH") "RF")
      )
      (libsource (lib "Integrated_Library_FEDEVEL_APR_2015") (part "RC0805FR-0710KL"))
    )
    (comp (ref "R5")
      (value "22R")
      (footprint "R0805")
      (description "RES SMD 22 OHM 1% 1/8W 0805")
      (fields
        (field (name "MANUFACTURER") "Yageo")
        (field (name "MANUFACTURER PART NUMBER") "RC0805FR-0722RL")
        (field (name ".CREATOR") "MM")
        (field (name ".CHECKED PCB") "RF")
        (field (name ".CHECKED SCH") "RF")
      )
      (libsource (lib "Integrated_Library_FEDEVEL_APR_2015") (part "RC0805FR-0722RL"))
    )
    (comp (ref "R6")
      (value "22R")
      (footprint "R0805")
      (description "RES SMD 22 OHM 1% 1/8W 0805")
      (fields
        (field (name "MANUFACTURER") "Yageo")
        (field (name "MANUFACTURER PART NUMBER") "RC0805FR-0722RL")
        (field (name ".CREATOR") "MM")
        (field (name ".CHECKED PCB") "RF")
        (field (name ".CHECKED SCH") "RF")
      )
      (libsource (lib "Integrated_Library_FEDEVEL_APR_2015") (part "RC0805FR-0722RL"))
    )
    (comp (ref "R7")
      (value "22R")
      (footprint "R0805")
      (description "RES SMD 22 OHM 1% 1/8W 0805")
      (fields
        (field (name "MANUFACTURER") "Yageo")
        (field (name "MANUFACTURER PART NUMBER") "RC0805FR-0722RL")
        (field (name ".CREATOR") "MM")
        (field (name ".CHECKED PCB") "RF")
        (field (name ".CHECKED SCH") "RF")
      )
      (libsource (lib "Integrated_Library_FEDEVEL_APR_2015") (part "RC0805FR-0722RL"))
    )
    (comp (ref "R8")
      (value "0R")
      (footprint "R0805")
      (description "RES 0.0 OHM 1/8W 0805 SMD")
      (fields
        (field (name "MANUFACTURER") "Yageo")
        (field (name "MANUFACTURER PART NUMBER") "RC0805JR-070RL")
        (field (name ".CHECKED PCB") "RF")
        (field (name ".CHECKED SCH") "RF")
      )
      (libsource (lib "Integrated_Library_FEDEVEL_APR_2015") (part "RC0805JR-070RL"))
    )
    (comp (ref "R9")
      (value "1M")
      (footprint "R0805")
      (description "RES SMD 1M OHM 1% 1/8W 0805")
      (fields
        (field (name "MANUFACTURER") "Yageo")
        (field (name "MANUFACTURER PART NUMBER") "RC0805FR-071ML")
        (field (name ".CREATOR") "MM")
        (field (name ".CHECKED PCB") "RF")
        (field (name ".CHECKED SCH") "RF")
      )
      (libsource (lib "Integrated_Library_FEDEVEL_APR_2015") (part "RC0805FR-071ML"))
    )
    (comp (ref "R10")
      (value "1k")
      (footprint "R0805")
      (description "RES SMD 1K OHM 1% 1/8W 0805")
      (fields
        (field (name "MANUFACTURER") "Yageo")
        (field (name "MANUFACTURER PART NUMBER") "RC0805FR-071KL")
        (field (name ".CREATOR") "MM")
        (field (name ".CHECKED PCB") "RF")
        (field (name ".CHECKED SCH") "RF")
      )
      (libsource (lib "Integrated_Library_FEDEVEL_APR_2015") (part "RC0805FR-071KL"))
    )
    (comp (ref "R11")
      (value "1k")
      (footprint "R0805")
      (description "RES SMD 1K OHM 1% 1/8W 0805")
      (fields
        (field (name "MANUFACTURER") "Yageo")
        (field (name "MANUFACTURER PART NUMBER") "RC0805FR-071KL")
        (field (name ".CREATOR") "MM")
        (field (name ".CHECKED PCB") "RF")
        (field (name ".CHECKED SCH") "RF")
      )
      (libsource (lib "Integrated_Library_FEDEVEL_APR_2015") (part "RC0805FR-071KL"))
    )
    (comp (ref "R12")
      (value "1k")
      (footprint "R0805")
      (description "RES SMD 1K OHM 1% 1/8W 0805")
      (fields
        (field (name "MANUFACTURER") "Yageo")
        (field (name "MANUFACTURER PART NUMBER") "RC0805FR-071KL")
        (field (name ".CREATOR") "MM")
        (field (name ".CHECKED PCB") "RF")
        (field (name ".CHECKED SCH") "RF")
      )
      (libsource (lib "Integrated_Library_FEDEVEL_APR_2015") (part "RC0805FR-071KL"))
    )
    (comp (ref "R13")
      (value "22R")
      (footprint "R0805")
      (description "RES SMD 22 OHM 1% 1/8W 0805")
      (fields
        (field (name "MANUFACTURER") "Yageo")
        (field (name "MANUFACTURER PART NUMBER") "RC0805FR-0722RL")
        (field (name ".CREATOR") "MM")
        (field (name ".CHECKED PCB") "RF")
        (field (name ".CHECKED SCH") "RF")
      )
      (libsource (lib "Integrated_Library_FEDEVEL_APR_2015") (part "RC0805FR-0722RL"))
    )
    (comp (ref "R14")
      (value "10k")
      (footprint "R0805")
      (description "RES SMD 10K OHM 1% 1/8W 0805")
      (fields
        (field (name "MANUFACTURER") "Yageo")
        (field (name "MANUFACTURER PART NUMBER") "RC0805FR-0710KL")
        (field (name ".CREATOR") "MM")
        (field (name ".CHECKED PCB") "RF")
        (field (name ".CHECKED SCH") "RF")
      )
      (libsource (lib "Integrated_Library_FEDEVEL_APR_2015") (part "RC0805FR-0710KL"))
    )
    (comp (ref "R15")
      (value "560R")
      (footprint "R0805")
      (description "RES SMD 560 OHM 1% 1/8W 0805")
      (fields
        (field (name "MANUFACTURER") "Yageo")
        (field (name "MANUFACTURER PART NUMBER") "RC0805FR-07560RL")
        (field (name ".CREATOR") "MM")
        (field (name ".CHECKED PCB") "RF")
        (field (name ".CHECKED SCH") "RF")
      )
      (libsource (lib "Integrated_Library_FEDEVEL_APR_2015") (part "RC0805FR-07560RL"))
    )
    (comp (ref "R16")
      (value "1M")
      (footprint "R0805")
      (description "RES SMD 1M OHM 1% 1/8W 0805")
      (fields
        (field (name "MANUFACTURER") "Yageo")
        (field (name "MANUFACTURER PART NUMBER") "RC0805FR-071ML")
        (field (name ".CREATOR") "MM")
        (field (name ".CHECKED PCB") "RF")
        (field (name ".CHECKED SCH") "RF")
      )
      (libsource (lib "Integrated_Library_FEDEVEL_APR_2015") (part "RC0805FR-071ML"))
    )
    (comp (ref "R17")
      (value "560R")
      (footprint "R0805")
      (description "RES SMD 560 OHM 1% 1/8W 0805")
      (fields
        (field (name "MANUFACTURER") "Yageo")
        (field (name "MANUFACTURER PART NUMBER") "RC0805FR-07560RL")
        (field (name ".CREATOR") "MM")
        (field (name ".CHECKED PCB") "RF")
        (field (name ".CHECKED SCH") "RF")
      )
      (libsource (lib "Integrated_Library_FEDEVEL_APR_2015") (part "RC0805FR-07560RL"))
    )
    (comp (ref "R18")
      (value "10k")
      (footprint "R0805")
      (description "RES SMD 10K OHM 1% 1/8W 0805")
      (fields
        (field (name "MANUFACTURER") "Yageo")
        (field (name "MANUFACTURER PART NUMBER") "RC0805FR-0710KL")
        (field (name ".CREATOR") "MM")
        (field (name ".CHECKED PCB") "RF")
        (field (name ".CHECKED SCH") "RF")
      )
      (libsource (lib "Integrated_Library_FEDEVEL_APR_2015") (part "RC0805FR-0710KL"))
    )
    (comp (ref "R19")
      (value "10k")
      (footprint "R0805")
      (description "RES SMD 10K OHM 1% 1/8W 0805")
      (fields
        (field (name "MANUFACTURER") "Yageo")
        (field (name "MANUFACTURER PART NUMBER") "RC0805FR-0710KL")
        (field (name ".CREATOR") "MM")
        (field (name ".CHECKED PCB") "RF")
        (field (name ".CHECKED SCH") "RF")
      )
      (libsource (lib "Integrated_Library_FEDEVEL_APR_2015") (part "RC0805FR-0710KL"))
    )
    (comp (ref "R20")
      (value "10k")
      (footprint "R0805")
      (description "RES SMD 10K OHM 1% 1/8W 0805")
      (fields
        (field (name "MANUFACTURER") "Yageo")
        (field (name "MANUFACTURER PART NUMBER") "RC0805FR-0710KL")
        (field (name ".CREATOR") "MM")
        (field (name ".CHECKED PCB") "RF")
        (field (name ".CHECKED SCH") "RF")
      )
      (libsource (lib "Integrated_Library_FEDEVEL_APR_2015") (part "RC0805FR-0710KL"))
    )
    (comp (ref "R21")
      (value "10k")
      (footprint "R0805")
      (description "RES SMD 10K OHM 1% 1/8W 0805")
      (fields
        (field (name "MANUFACTURER") "Yageo")
        (field (name "MANUFACTURER PART NUMBER") "RC0805FR-0710KL")
        (field (name ".CREATOR") "MM")
        (field (name ".CHECKED PCB") "RF")
        (field (name ".CHECKED SCH") "RF")
      )
      (libsource (lib "Integrated_Library_FEDEVEL_APR_2015") (part "RC0805FR-0710KL"))
    )
    (comp (ref "R22")
      (value "560R")
      (footprint "R0805")
      (description "RES SMD 560 OHM 1% 1/8W 0805")
      (fields
        (field (name "MANUFACTURER") "Yageo")
        (field (name "MANUFACTURER PART NUMBER") "RC0805FR-07560RL")
        (field (name ".CREATOR") "MM")
        (field (name ".CHECKED PCB") "RF")
        (field (name ".CHECKED SCH") "RF")
      )
      (libsource (lib "Integrated_Library_FEDEVEL_APR_2015") (part "RC0805FR-07560RL"))
    )
    (comp (ref "R23")
      (value "22R")
      (footprint "R0805")
      (description "RES SMD 22 OHM 1% 1/8W 0805")
      (fields
        (field (name "MANUFACTURER") "Yageo")
        (field (name "MANUFACTURER PART NUMBER") "RC0805FR-0722RL")
        (field (name ".CREATOR") "MM")
        (field (name ".CHECKED PCB") "RF")
        (field (name ".CHECKED SCH") "RF")
      )
      (libsource (lib "Integrated_Library_FEDEVEL_APR_2015") (part "RC0805FR-0722RL"))
    )
    (comp (ref "R24")
      (value "22R")
      (footprint "R0805")
      (description "RES SMD 22 OHM 1% 1/8W 0805")
      (fields
        (field (name "MANUFACTURER") "Yageo")
        (field (name "MANUFACTURER PART NUMBER") "RC0805FR-0722RL")
        (field (name ".CREATOR") "MM")
        (field (name ".CHECKED PCB") "RF")
        (field (name ".CHECKED SCH") "RF")
      )
      (libsource (lib "Integrated_Library_FEDEVEL_APR_2015") (part "RC0805FR-0722RL"))
    )
    (comp (ref "R25")
      (value "22R")
      (footprint "R0805")
      (description "RES SMD 22 OHM 1% 1/8W 0805")
      (fields
        (field (name "MANUFACTURER") "Yageo")
        (field (name "MANUFACTURER PART NUMBER") "RC0805FR-0722RL")
        (field (name ".CREATOR") "MM")
        (field (name ".CHECKED PCB") "RF")
        (field (name ".CHECKED SCH") "RF")
      )
      (libsource (lib "Integrated_Library_FEDEVEL_APR_2015") (part "RC0805FR-0722RL"))
    )
    (comp (ref "R26")
      (value "0R")
      (footprint "R0805")
      (description "RES 0.0 OHM 1/8W 0805 SMD")
      (fields
        (field (name "MANUFACTURER") "Yageo")
        (field (name "MANUFACTURER PART NUMBER") "RC0805JR-070RL")
        (field (name ".CHECKED PCB") "RF")
        (field (name ".CHECKED SCH") "RF")
      )
      (libsource (lib "Integrated_Library_FEDEVEL_APR_2015") (part "RC0805JR-070RL"))
    )
    (comp (ref "R27")
      (value "0R")
      (footprint "R0805")
      (description "RES 0.0 OHM 1/8W 0805 SMD")
      (fields
        (field (name "MANUFACTURER") "Yageo")
        (field (name "MANUFACTURER PART NUMBER") "RC0805JR-070RL")
        (field (name ".CHECKED PCB") "RF")
        (field (name ".CHECKED SCH") "RF")
      )
      (libsource (lib "Integrated_Library_FEDEVEL_APR_2015") (part "RC0805JR-070RL"))
    )
    (comp (ref "R28")
      (value "0R")
      (footprint "R0805")
      (description "RES 0.0 OHM 1/8W 0805 SMD")
      (fields
        (field (name "MANUFACTURER") "Yageo")
        (field (name "MANUFACTURER PART NUMBER") "RC0805JR-070RL")
        (field (name ".CHECKED PCB") "RF")
        (field (name ".CHECKED SCH") "RF")
      )
      (libsource (lib "Integrated_Library_FEDEVEL_APR_2015") (part "RC0805JR-070RL"))
    )
    (comp (ref "SCKT FOR U1")
      (value "28-DIP Socket")
      (footprint "28_DIP_7.62mm_SOCKET")
      (description "CONN IC DIP SOCKET 28POS TIN")
      (fields
        (field (name "MANUFACTURER") "3M")
        (field (name "MANUFACTURER PART NUMBER") "4828-3004-CP")
        (field (name ".CREATOR") "MM")
        (field (name ".CHECKED PCB") "RF")
        (field (name ".CHECKED SCH") "RF")
      )
      (libsource (lib "Integrated_Library_FEDEVEL_APR_2015") (part "4828-3004-CP"))
    )
    (comp (ref "SW1")
      (value "1825910-6")
      (footprint "1825910-6")
      (description "SWITCH TACTILE SPST-NO 0.05A 24V")
      (fields
        (field (name "MANUFACTURER") "TE Connectivity")
        (field (name ".CREATOR") "MM")
        (field (name ".CHECKED PCB") "RF")
        (field (name ".CHECKED SCH") "RF")
      )
      (libsource (lib "Integrated_Library_FEDEVEL_APR_2015") (part "1825910-6"))
    )
    (comp (ref "SW2")
      (value "1825910-6")
      (footprint "1825910-6")
      (description "SWITCH TACTILE SPST-NO 0.05A 24V")
      (fields
        (field (name "MANUFACTURER") "TE Connectivity")
        (field (name ".CREATOR") "MM")
        (field (name ".CHECKED PCB") "RF")
        (field (name ".CHECKED SCH") "RF")
      )
      (libsource (lib "Integrated_Library_FEDEVEL_APR_2015") (part "1825910-6"))
    )
    (comp (ref "U1")
      (value "ATMEGA328P-PU")
      (footprint "28_DIP_7.62mm")
      (description "IC MCU 8BIT 32KB FLASH 28DIP")
      (fields
        (field (name "MANUFACTURER") "Atmel")
        (field (name ".CREATOR") "MM")
        (field (name ".CHECKED PCB") "RF")
        (field (name ".CHECKED SCH") "RF")
      )
      (libsource (lib "Integrated_Library_FEDEVEL_APR_2015") (part "ATMEGA328P-PU"))
    )
    (comp (ref "U2")
      (value "ATMEGA16U2-AU")
      (footprint "TQFP32")
      (description "IC MCU 8BIT 16KB FLASH 32TQFP")
      (fields
        (field (name "MANUFACTURER") "Atmel")
        (field (name ".CREATOR") "MM")
        (field (name ".CHECKED PCB") "RF")
        (field (name ".CHECKED SCH") "RF")
      )
      (libsource (lib "Integrated_Library_FEDEVEL_APR_2015") (part "ATMEGA16U2-AU"))
    )
    (comp (ref "U3")
      (value "TL1963A-33DCQR")
      (footprint "DCQ (R-PDSO-G6)")
      (description "IC REG LDO 3.3V 1.5A SOT223-6")
      (fields
        (field (name "MANUFACTURER") "Texas Instruments")
        (field (name ".CREATOR") "MM")
        (field (name ".CHECKED PCB") "RF")
        (field (name ".CHECKED SCH") "RF")
      )
      (libsource (lib "Integrated_Library_FEDEVEL_APR_2015") (part "TL1963A-33DCQR"))
    )
    (comp (ref "U4")
      (value "SN74AHC1G09DBVR")
      (footprint "DBV_SOT_23_5")
      (description "IC GATE AND SGL 2INP SOT23-5")
      (fields (field (name "MANUFACTURER") "Texas Instruments") (field (name ".CREATOR") "MM"))
      (libsource (lib "Integrated_Library_FEDEVEL_APR_2015") (part "SN74AHC1G09DBVR"))
    )
    (comp (ref "U5")
      (value "SN74AHC1G09DBVR")
      (footprint "DBV_SOT_23_5")
      (description "IC GATE AND SGL 2INP SOT23-5")
      (fields (field (name "MANUFACTURER") "Texas Instruments") (field (name ".CREATOR") "MM"))
      (libsource (lib "Integrated_Library_FEDEVEL_APR_2015") (part "SN74AHC1G09DBVR"))
    )
    (comp (ref "U6")
      (value "SN74AHC1G09DBVR")
      (footprint "DBV_SOT_23_5")
      (description "IC GATE AND SGL 2INP SOT23-5")
      (fields (field (name "MANUFACTURER") "Texas Instruments") (field (name ".CREATOR") "MM"))
      (libsource (lib "Integrated_Library_FEDEVEL_APR_2015") (part "SN74AHC1G09DBVR"))
    )
    (comp (ref "U7")
      (value "SN74AHC1G09DBVR")
      (footprint "DBV_SOT_23_5")
      (description "IC GATE AND SGL 2INP SOT23-5")
      (fields (field (name "MANUFACTURER") "Texas Instruments") (field (name ".CREATOR") "MM"))
      (libsource (lib "Integrated_Library_FEDEVEL_APR_2015") (part "SN74AHC1G09DBVR"))
    )
    (comp (ref "Y1")
      (value "ABM7-16.000MHZ-D2Y-T")
      (footprint "ABM7_v1_1_BIG")
      (description "CRYSTAL 16MHZ 18PF SMD")
      (fields
        (field (name "MANUFACTURER") "Abracon LLC")
        (field (name ".CREATOR") "MM")
        (field (name ".CHECKED PCB") "RF")
        (field (name ".CHECKED SCH") "RF")
      )
      (libsource (lib "Integrated_Library_FEDEVEL_APR_2015") (part "ABM7-16.000MHZ-D2Y-T"))
    )
    (comp (ref "Y2")
      (value "ABM7-16.000MHZ-D2Y-T")
      (footprint "ABM7_v1_1_BIG")
      (description "CRYSTAL 16MHZ 18PF SMD")
      (fields
        (field (name "MANUFACTURER") "Abracon LLC")
        (field (name ".CREATOR") "MM")
        (field (name ".CHECKED PCB") "RF")
        (field (name ".CHECKED SCH") "RF")
      )
      (libsource (lib "Integrated_Library_FEDEVEL_APR_2015") (part "ABM7-16.000MHZ-D2Y-T"))
    )
    (comp (ref "Z1")
      (value "CG0603MLC-05E")
      (footprint "R0603")
      (description "VARISTOR 0603")
      (fields
        (field (name "MANUFACTURER") "Bourns Inc.")
        (field (name ".CREATOR") "MM")
        (field (name ".CHECKED PCB") "RF")
        (field (name ".CHECKED SCH") "RF")
      )
      (libsource (lib "Integrated_Library_FEDEVEL_APR_2015") (part "CG0603MLC-05E"))
    )
    (comp (ref "Z2")
      (value "CG0603MLC-05E")
      (footprint "R0603")
      (description "VARISTOR 0603")
      (fields
        (field (name "MANUFACTURER") "Bourns Inc.")
        (field (name ".CREATOR") "MM")
        (field (name ".CHECKED PCB") "RF")
        (field (name ".CHECKED SCH") "RF")
      )
      (libsource (lib "Integrated_Library_FEDEVEL_APR_2015") (part "CG0603MLC-05E"))
    )
  )
  (nets
    (net (code "1") (name "+3V3") (class "Default")
      (node (ref "C13") (pin "1") (pinfunction "1_1") (pintype "passive"))
      (node (ref "C16") (pin "1") (pinfunction "1_1") (pintype "passive"))
      (node (ref "J1") (pin "4") (pinfunction "4_4") (pintype "passive"))
      (node (ref "JP4") (pin "3") (pinfunction "3_3") (pintype "passive"))
      (node (ref "R28") (pin "1") (pinfunction "1_1") (pintype "passive"))
      (node (ref "U3") (pin "4") (pinfunction "OUT_4") (pintype "passive"))
      (node (ref "U3") (pin "5") (pinfunction "SENSE_5") (pintype "passive"))
    )
    (net (code "2") (name "+5V") (class "Default")
      (node (ref "C14") (pin "1") (pinfunction "1_1") (pintype "passive"))
      (node (ref "C2") (pin "1") (pinfunction "1_1") (pintype "passive"))
      (node (ref "C6") (pin "1") (pinfunction "1_1") (pintype "passive"))
      (node (ref "J1") (pin "5") (pinfunction "5_5") (pintype "passive"))
      (node (ref "J8") (pin "1") (pinfunction "1_1") (pintype "passive"))
      (node (ref "JP4") (pin "1") (pinfunction "1_1") (pintype "passive"))
      (node (ref "L1") (pin "2") (pinfunction "2_2") (pintype "passive"))
      (node (ref "R27") (pin "2") (pinfunction "2_2") (pintype "passive"))
      (node (ref "U2") (pin "31") (pinfunction "UVCC_31") (pintype "passive"))
    )
    (net (code "3") (name "+5V{slash}3V3") (class "Default")
      (node (ref "C15") (pin "1") (pinfunction "1_1") (pintype "passive"))
      (node (ref "C17") (pin "1") (pinfunction "1_1") (pintype "passive"))
      (node (ref "C26") (pin "1") (pinfunction "1_1") (pintype "passive"))
      (node (ref "C28") (pin "1") (pinfunction "1_1") (pintype "passive"))
      (node (ref "C29") (pin "1") (pinfunction "1_1") (pintype "passive"))
      (node (ref "C30") (pin "1") (pinfunction "1_1") (pintype "passive"))
      (node (ref "C34") (pin "1") (pinfunction "1_1") (pintype "passive"))
      (node (ref "C8") (pin "1") (pinfunction "1_1") (pintype "passive"))
      (node (ref "D5") (pin "1") (pinfunction "Cathode_1") (pintype "passive"))
      (node (ref "D6") (pin "1") (pinfunction "Cathode_1") (pintype "passive"))
      (node (ref "FB1") (pin "1") (pinfunction "1_1") (pintype "passive"))
      (node (ref "FB2") (pin "1") (pinfunction "1_1") (pintype "passive"))
      (node (ref "FB3") (pin "1") (pinfunction "1_1") (pintype "passive"))
      (node (ref "J1") (pin "2") (pinfunction "2_2") (pintype "passive"))
      (node (ref "J5") (pin "2") (pinfunction "2_2") (pintype "passive"))
      (node (ref "J6") (pin "2") (pinfunction "2_2") (pintype "passive"))
      (node (ref "JP4") (pin "2") (pinfunction "2_2") (pintype "passive"))
      (node (ref "R1") (pin "2") (pinfunction "2_2") (pintype "passive"))
      (node (ref "R14") (pin "2") (pinfunction "2_2") (pintype "passive"))
      (node (ref "R15") (pin "2") (pinfunction "2_2") (pintype "passive"))
      (node (ref "R17") (pin "2") (pinfunction "2_2") (pintype "passive"))
      (node (ref "R18") (pin "2") (pinfunction "2_2") (pintype "passive"))
      (node (ref "R19") (pin "2") (pinfunction "2_2") (pintype "passive"))
      (node (ref "R2") (pin "2") (pinfunction "2_2") (pintype "passive"))
      (node (ref "R20") (pin "2") (pinfunction "2_2") (pintype "passive"))
      (node (ref "R21") (pin "2") (pinfunction "2_2") (pintype "passive"))
      (node (ref "R27") (pin "1") (pinfunction "1_1") (pintype "passive"))
      (node (ref "R28") (pin "2") (pinfunction "2_2") (pintype "passive"))
      (node (ref "R3") (pin "2") (pinfunction "2_2") (pintype "passive"))
      (node (ref "R4") (pin "2") (pinfunction "2_2") (pintype "passive"))
      (node (ref "U4") (pin "5") (pinfunction "VCC_5") (pintype "power_in"))
      (node (ref "U5") (pin "5") (pinfunction "VCC_5") (pintype "power_in"))
      (node (ref "U6") (pin "5") (pinfunction "VCC_5") (pintype "power_in"))
      (node (ref "U7") (pin "5") (pinfunction "VCC_5") (pintype "power_in"))
    )
    (net (code "4") (name "+AREF") (class "Default")
      (node (ref "C21") (pin "1") (pinfunction "1_1") (pintype "passive"))
      (node (ref "C24") (pin "1") (pinfunction "1_1") (pintype "passive"))
      (node (ref "J4") (pin "8") (pinfunction "8_8") (pintype "passive"))
      (node (ref "U1") (pin "21") (pinfunction "AREF_21") (pintype "passive"))
    )
    (net (code "5") (name "/+3V3_16U2_UCAP") (class "Default")
      (node (ref "C7") (pin "2") (pinfunction "2_2") (pintype "passive"))
      (node (ref "R26") (pin "1") (pinfunction "1_1") (pintype "passive"))
      (node (ref "U2") (pin "27") (pinfunction "UCAP_27") (pintype "passive"))
    )
    (net (code "6") (name "/+5V_USB") (class "Default")
      (node (ref "C1") (pin "1") (pinfunction "1_1") (pintype "passive"))
      (node (ref "J7") (pin "1") (pinfunction "P1_1") (pintype "passive"))
      (node (ref "L1") (pin "1") (pinfunction "1_1") (pintype "passive"))
    )
    (net (code "7") (name "/+5V{slash}3V3_16U2") (class "Default")
      (node (ref "C3") (pin "1") (pinfunction "1_1") (pintype "passive"))
      (node (ref "C4") (pin "1") (pinfunction "1_1") (pintype "passive"))
      (node (ref "C5") (pin "1") (pinfunction "1_1") (pintype "passive"))
      (node (ref "FB1") (pin "2") (pinfunction "2_2") (pintype "passive"))
      (node (ref "R26") (pin "2") (pinfunction "2_2") (pintype "passive"))
      (node (ref "U2") (pin "32") (pinfunction "AVCC_32") (pintype "passive"))
      (node (ref "U2") (pin "4") (pinfunction "VCC_4") (pintype "passive"))
    )
    (net (code "8") (name "/+5V{slash}3V3_328P_AVCC") (class "Default")
      (node (ref "C22") (pin "1") (pinfunction "1_1") (pintype "passive"))
      (node (ref "C23") (pin "1") (pinfunction "1_1") (pintype "passive"))
      (node (ref "FB3") (pin "2") (pinfunction "2_2") (pintype "passive"))
      (node (ref "U1") (pin "20") (pinfunction "AVCC_20") (pintype "passive"))
    )
    (net (code "9") (name "/+5V{slash}3V3_328P_VCC") (class "Default")
      (node (ref "C19") (pin "1") (pinfunction "1_1") (pintype "passive"))
      (node (ref "C20") (pin "1") (pinfunction "1_1") (pintype "passive"))
      (node (ref "FB2") (pin "2") (pinfunction "2_2") (pintype "passive"))
      (node (ref "U1") (pin "7") (pinfunction "VCC_7") (pintype "passive"))
    )
    (net (code "10") (name "/16U2PROG_328P_RESETn") (class "Default")
      (node (ref "JP1") (pin "2") (pinfunction "2_2") (pintype "passive"))
      (node (ref "R1") (pin "1") (pinfunction "1_1") (pintype "passive"))
      (node (ref "U2") (pin "13") (pinfunction "~{CTS}_/~{_HWB}_/_T0_/_AIN6_/_INT7_/_PD7_13") (pintype "passive"))
    )
    (net (code "11") (name "/16U2_16MHZ_XTAL1") (class "Default")
      (node (ref "C10") (pin "2") (pinfunction "2_2") (pintype "passive"))
      (node (ref "R9") (pin "1") (pinfunction "1_1") (pintype "passive"))
      (node (ref "U2") (pin "1") (pinfunction "XTAL1_1") (pintype "passive"))
      (node (ref "Y2") (pin "1") (pinfunction "1_1") (pintype "passive"))
    )
    (net (code "12") (name "/16U2_16MHZ_XTAL2") (class "Default")
      (node (ref "C9") (pin "2") (pinfunction "2_2") (pintype "passive"))
      (node (ref "R9") (pin "2") (pinfunction "2_2") (pintype "passive"))
      (node (ref "U2") (pin "2") (pinfunction "XTAL2_/_PC0_2") (pintype "passive"))
      (node (ref "Y2") (pin "2") (pinfunction "2_2") (pintype "passive"))
    )
    (net (code "13") (name "/16U2_BUF_RESETn") (class "Default")
      (node (ref "C31") (pin "1") (pinfunction "1_1") (pintype "passive"))
      (node (ref "R23") (pin "2") (pinfunction "2_2") (pintype "passive"))
      (node (ref "U5") (pin "1") (pinfunction "A_1") (pintype "passive"))
      (node (ref "U5") (pin "2") (pinfunction "B_2") (pintype "passive"))
    )
    (net (code "14") (name "/16U2_HDR_RESETn") (class "Default")
      (node (ref "J6") (pin "5") (pinfunction "5_5") (pintype "passive"))
      (node (ref "JP3") (pin "3") (pinfunction "3_3") (pintype "passive"))
    )
    (net (code "15") (name "/16U2_MISO") (class "Default")
      (node (ref "J6") (pin "1") (pinfunction "1_1") (pintype "passive"))
      (node (ref "U2") (pin "17") (pinfunction "PDO_/_MISO_/_PCINT3_/_PB3_17") (pintype "passive"))
    )
    (net (code "16") (name "/16U2_MOSI") (class "Default")
      (node (ref "J6") (pin "4") (pinfunction "4_4") (pintype "passive"))
      (node (ref "U2") (pin "16") (pinfunction "PDI_/_MOSI_/_PCINT2_/_PB2_16") (pintype "passive"))
    )
    (net (code "17") (name "/16U2_PB4") (class "Default")
      (node (ref "JP2") (pin "1") (pinfunction "1_1") (pintype "passive"))
      (node (ref "JP3") (pin "2") (pinfunction "2_2") (pintype "passive"))
      (node (ref "U2") (pin "18") (pinfunction "T1_/_PCINT4_/_PB4_18") (pintype "passive"))
    )
    (net (code "18") (name "/16U2_PB5") (class "Default")
      (node (ref "JP2") (pin "3") (pinfunction "3_3") (pintype "passive"))
      (node (ref "U2") (pin "19") (pinfunction "PCINT5_/_PB5_19") (pintype "passive"))
    )
    (net (code "19") (name "/16U2_PB6") (class "Default")
      (node (ref "JP2") (pin "2") (pinfunction "2_2") (pintype "passive"))
      (node (ref "U2") (pin "20") (pinfunction "PCINT6_/_PB6_20") (pintype "passive"))
    )
    (net (code "20") (name "/16U2_PB7") (class "Default")
      (node (ref "JP2") (pin "4") (pinfunction "4_4") (pintype "passive"))
      (node (ref "U2") (pin "21") (pinfunction "OC.0A_/_OC.1C_/_PCINT7_/_PB7_21") (pintype "passive"))
    )
    (net (code "21") (name "/16U2_RESETn") (class "Default")
      (node (ref "JP3") (pin "4") (pinfunction "4_4") (pintype "passive"))
      (node (ref "R4") (pin "1") (pinfunction "1_1") (pintype "passive"))
      (node (ref "U2") (pin "24") (pinfunction "PC1_/~{_RESET}_/_DW_24") (pintype "passive"))
      (node (ref "U5") (pin "4") (pinfunction "Y_4") (pintype "passive"))
    )
    (net (code "22") (name "/16U2_RXD") (class "Default")
      (node (ref "R11") (pin "1") (pinfunction "1_1") (pintype "passive"))
      (node (ref "U2") (pin "8") (pinfunction "RXD1_/_AIN1_/_INT2_/_PD2_8") (pintype "passive"))
    )
    (net (code "23") (name "/16U2_RX_LED") (class "Default")
      (node (ref "D4") (pin "1") (pinfunction "cathode_1") (pintype "passive"))
      (node (ref "U2") (pin "10") (pinfunction "AIN3_/_INT5_/_PD4_10") (pintype "passive"))
    )
    (net (code "24") (name "/16U2_SCLK") (class "Default")
      (node (ref "J6") (pin "3") (pinfunction "3_3") (pintype "passive"))
      (node (ref "R5") (pin "2") (pinfunction "2_2") (pintype "passive"))
    )
    (net (code "25") (name "/16U2_SCLK_R") (class "Default")
      (node (ref "R5") (pin "1") (pinfunction "1_1") (pintype "passive"))
      (node (ref "U2") (pin "15") (pinfunction "SCLK_/_PCINT1_/_PB1_15") (pintype "passive"))
    )
    (net (code "26") (name "/16U2_TXD") (class "Default")
      (node (ref "R10") (pin "1") (pinfunction "1_1") (pintype "passive"))
      (node (ref "U2") (pin "9") (pinfunction "TXD1_/_INT3_/_PD3_9") (pintype "passive"))
    )
    (net (code "27") (name "/16U2_TX_LED") (class "Default")
      (node (ref "D3") (pin "1") (pinfunction "cathode_1") (pintype "passive"))
      (node (ref "U2") (pin "11") (pinfunction "XCK_/_AIN4_/_PCINT12_/_PD5_11") (pintype "passive"))
    )
    (net (code "28") (name "/328P_16MHZ_XTAL1") (class "Default")
      (node (ref "C27") (pin "2") (pinfunction "2_2") (pintype "passive"))
      (node (ref "R16") (pin "1") (pinfunction "1_1") (pintype "passive"))
      (node (ref "U1") (pin "9") (pinfunction "PB6_/_PCINT6_/_TOSC1_/_XTAL1_9") (pintype "passive"))
      (node (ref "Y1") (pin "1") (pinfunction "1_1") (pintype "passive"))
    )
    (net (code "29") (name "/328P_16MHZ_XTAL2") (class "Default")
      (node (ref "C25") (pin "2") (pinfunction "2_2") (pintype "passive"))
      (node (ref "R16") (pin "2") (pinfunction "2_2") (pintype "passive"))
      (node (ref "U1") (pin "10") (pinfunction "PB7_/_PCINT7_/_TOSC2_/_XTAL2_10") (pintype "passive"))
      (node (ref "Y1") (pin "2") (pinfunction "2_2") (pintype "passive"))
    )
    (net (code "30") (name "/328P_AUTORESETn") (class "Default")
      (node (ref "C11") (pin "1") (pinfunction "1_1") (pintype "passive"))
      (node (ref "R18") (pin "1") (pinfunction "1_1") (pintype "passive"))
      (node (ref "U6") (pin "1") (pinfunction "A_1") (pintype "passive"))
    )
    (net (code "31") (name "/328P_BUF_RESETn") (class "Default")
      (node (ref "C32") (pin "1") (pinfunction "1_1") (pintype "passive"))
      (node (ref "R24") (pin "2") (pinfunction "2_2") (pintype "passive"))
      (node (ref "U6") (pin "2") (pinfunction "B_2") (pintype "passive"))
    )
    (net (code "32") (name "/328P_RESETn") (class "Default")
      (node (ref "J1") (pin "3") (pinfunction "3_3") (pintype "passive"))
      (node (ref "J5") (pin "5") (pinfunction "5_5") (pintype "passive"))
      (node (ref "JP3") (pin "1") (pinfunction "1_1") (pintype "passive"))
      (node (ref "R14") (pin "1") (pinfunction "1_1") (pintype "passive"))
      (node (ref "U1") (pin "1") (pinfunction "PC6_/_PCINT14_/~{_RESET}_1") (pintype "passive"))
      (node (ref "U6") (pin "4") (pinfunction "Y_4") (pintype "passive"))
    )
    (net (code "33") (name "/AD0") (class "Default")
      (node (ref "J2") (pin "1") (pinfunction "1_1") (pintype "passive"))
      (node (ref "U1") (pin "23") (pinfunction "PCINT8_/_ADC0_/_PC0_23") (pintype "passive"))
    )
    (net (code "34") (name "/AD1") (class "Default")
      (node (ref "J2") (pin "2") (pinfunction "2_2") (pintype "passive"))
      (node (ref "U1") (pin "24") (pinfunction "PCINT9_/_ADC1_/_PC1_24") (pintype "passive"))
    )
    (net (code "35") (name "/AD2") (class "Default")
      (node (ref "J2") (pin "3") (pinfunction "3_3") (pintype "passive"))
      (node (ref "U1") (pin "25") (pinfunction "PCINT10_/_ADC2_/_PC2_25") (pintype "passive"))
    )
    (net (code "36") (name "/AD3") (class "Default")
      (node (ref "J2") (pin "4") (pinfunction "4_4") (pintype "passive"))
      (node (ref "U1") (pin "26") (pinfunction "PCINT11_/_ADC3_/_PC3_26") (pintype "passive"))
    )
    (net (code "37") (name "/AD4{slash}SDA") (class "Default")
      (node (ref "J2") (pin "5") (pinfunction "5_5") (pintype "passive"))
      (node (ref "J4") (pin "9") (pinfunction "9_9") (pintype "passive"))
      (node (ref "U1") (pin "27") (pinfunction "SDA_/_PCINT12_/_ADC4_/_PC4_27") (pintype "passive"))
    )
    (net (code "38") (name "/AD5{slash}SCL") (class "Default")
      (node (ref "J2") (pin "6") (pinfunction "6_6") (pintype "passive"))
      (node (ref "J4") (pin "10") (pinfunction "10_10") (pintype "passive"))
      (node (ref "U1") (pin "28") (pinfunction "SCL_/_PCINT13_/_ADC5_/_PC5_28") (pintype "passive"))
    )
    (net (code "39") (name "/BUTTON_RESETn") (class "Default")
      (node (ref "D6") (pin "2") (pinfunction "Anode_2") (pintype "passive"))
      (node (ref "R20") (pin "1") (pinfunction "1_1") (pintype "passive"))
      (node (ref "R24") (pin "1") (pinfunction "1_1") (pintype "passive"))
      (node (ref "SW1") (pin "1") (pinfunction "1_1") (pintype "passive"))
      (node (ref "SW1") (pin "2") (pinfunction "2_2") (pintype "passive"))
    )
    (net (code "40") (name "/CON_USB_N") (class "Default")
      (node (ref "J7") (pin "2") (pinfunction "P2_2") (pintype "passive"))
      (node (ref "R6") (pin "1") (pinfunction "1_1") (pintype "passive"))
      (node (ref "Z1") (pin "2") (pinfunction "2_2") (pintype "passive"))
    )
    (net (code "41") (name "/CON_USB_P") (class "Default")
      (node (ref "J7") (pin "3") (pinfunction "P3_3") (pintype "passive"))
      (node (ref "R7") (pin "1") (pinfunction "1_1") (pintype "passive"))
      (node (ref "Z2") (pin "2") (pinfunction "2_2") (pintype "passive"))
    )
    (net (code "42") (name "/IO0") (class "Default")
      (node (ref "J3") (pin "1") (pinfunction "1_1") (pintype "passive"))
      (node (ref "R10") (pin "2") (pinfunction "2_2") (pintype "passive"))
      (node (ref "U1") (pin "2") (pinfunction "RXD_/_PCINT16_/_PD0_2") (pintype "passive"))
    )
    (net (code "43") (name "/IO1") (class "Default")
      (node (ref "J3") (pin "2") (pinfunction "2_2") (pintype "passive"))
      (node (ref "R11") (pin "2") (pinfunction "2_2") (pintype "passive"))
      (node (ref "U1") (pin "3") (pinfunction "TXD_/_PCINT17_/_PD1_3") (pintype "passive"))
    )
    (net (code "44") (name "/IO2") (class "Default")
      (node (ref "J3") (pin "3") (pinfunction "3_3") (pintype "passive"))
      (node (ref "U1") (pin "4") (pinfunction "INT0_/_PCINT18_/_PD2_4") (pintype "passive"))
    )
    (net (code "45") (name "/IO3") (class "Default")
      (node (ref "J3") (pin "4") (pinfunction "4_4") (pintype "passive"))
      (node (ref "U1") (pin "5") (pinfunction "OC2B_/_INT1_/_PCINT19_/_PD3_5") (pintype "passive"))
    )
    (net (code "46") (name "/IO4") (class "Default")
      (node (ref "J3") (pin "5") (pinfunction "5_5") (pintype "passive"))
      (node (ref "U1") (pin "6") (pinfunction "XCK_/_T0_/_PCINT20_/_PD4_6") (pintype "passive"))
    )
    (net (code "47") (name "/IO5") (class "Default")
      (node (ref "J3") (pin "6") (pinfunction "6_6") (pintype "passive"))
      (node (ref "U1") (pin "11") (pinfunction "OC0B_/_T1_/_PCINT21_/_PD5_11") (pintype "passive"))
    )
    (net (code "48") (name "/IO6") (class "Default")
      (node (ref "J3") (pin "7") (pinfunction "7_7") (pintype "passive"))
      (node (ref "U1") (pin "12") (pinfunction "OC0A_/_AIN0_/_PCINT22_/_PD6_12") (pintype "passive"))
    )
    (net (code "49") (name "/IO7") (class "Default")
      (node (ref "J3") (pin "8") (pinfunction "8_8") (pintype "passive"))
      (node (ref "U1") (pin "13") (pinfunction "AIN1_/_PCINT23_/_PD7_13") (pintype "passive"))
    )
    (net (code "50") (name "/IO8") (class "Default")
      (node (ref "J4") (pin "1") (pinfunction "1_1") (pintype "passive"))
      (node (ref "R22") (pin "1") (pinfunction "1_1") (pintype "passive"))
      (node (ref "U1") (pin "14") (pinfunction "CLKO_/_ICP1_/_PCINT0_/_PB0_14") (pintype "passive"))
    )
    (net (code "51") (name "/IO9") (class "Default")
      (node (ref "J4") (pin "2") (pinfunction "2_2") (pintype "passive"))
      (node (ref "U1") (pin "15") (pinfunction "OC1A_/_PCINT1_/_PB1_15") (pintype "passive"))
    )
    (net (code "52") (name "/MISO") (class "Default")
      (node (ref "J4") (pin "5") (pinfunction "5_5") (pintype "passive"))
      (node (ref "J5") (pin "1") (pinfunction "1_1") (pintype "passive"))
      (node (ref "U1") (pin "18") (pinfunction "MISO_/_PCINT4_/_PB4_18") (pintype "passive"))
    )
    (net (code "53") (name "/MOSI") (class "Default")
      (node (ref "J4") (pin "4") (pinfunction "4_4") (pintype "passive"))
      (node (ref "J5") (pin "4") (pinfunction "4_4") (pintype "passive"))
      (node (ref "U1") (pin "17") (pinfunction "MOSI_/_OC2A_/_PCINT3_/_PB3_17") (pintype "passive"))
    )
    (net (code "54") (name "/SCK") (class "Default")
      (node (ref "J4") (pin "6") (pinfunction "6_6") (pintype "passive"))
      (node (ref "J5") (pin "3") (pinfunction "3_3") (pintype "passive"))
      (node (ref "R13") (pin "2") (pinfunction "2_2") (pintype "passive"))
      (node (ref "U4") (pin "1") (pinfunction "A_1") (pintype "passive"))
      (node (ref "U4") (pin "2") (pinfunction "B_2") (pintype "passive"))
    )
    (net (code "55") (name "/SCK_R") (class "Default")
      (node (ref "R13") (pin "1") (pinfunction "1_1") (pintype "passive"))
      (node (ref "U1") (pin "19") (pinfunction "SCK_/_PCINT5_/_PB5_19") (pintype "passive"))
    )
    (net (code "56") (name "/SS") (class "Default")
      (node (ref "J4") (pin "3") (pinfunction "3_3") (pintype "passive"))
      (node (ref "U1") (pin "16") (pinfunction "~{SS}_/_OC1B_/_PCINT2_/_PB2_16") (pintype "passive"))
    )
    (net (code "57") (name "/USB_N") (class "Default")
      (node (ref "R6") (pin "2") (pinfunction "2_2") (pintype "passive"))
      (node (ref "U2") (pin "30") (pinfunction "D-_30") (pintype "passive"))
    )
    (net (code "58") (name "/USB_P") (class "Default")
      (node (ref "R7") (pin "2") (pinfunction "2_2") (pintype "passive"))
      (node (ref "U2") (pin "29") (pinfunction "D+_29") (pintype "passive"))
    )
    (net (code "59") (name "/USER_BUTTON") (class "Default")
      (node (ref "R21") (pin "1") (pinfunction "1_1") (pintype "passive"))
      (node (ref "R25") (pin "1") (pinfunction "1_1") (pintype "passive"))
      (node (ref "SW2") (pin "1") (pinfunction "1_1") (pintype "passive"))
      (node (ref "SW2") (pin "2") (pinfunction "2_2") (pintype "passive"))
    )
    (net (code "60") (name "/USER_BUTTON_BUF") (class "Default")
      (node (ref "C33") (pin "1") (pinfunction "1_1") (pintype "passive"))
      (node (ref "R25") (pin "2") (pinfunction "2_2") (pintype "passive"))
      (node (ref "U7") (pin "1") (pinfunction "A_1") (pintype "passive"))
      (node (ref "U7") (pin "2") (pinfunction "B_2") (pintype "passive"))
    )
    (net (code "61") (name "GND") (class "Default")
      (node (ref "C1") (pin "2") (pinfunction "2_2") (pintype "passive"))
      (node (ref "C10") (pin "1") (pinfunction "1_1") (pintype "passive"))
      (node (ref "C13") (pin "2") (pinfunction "2_2") (pintype "passive"))
      (node (ref "C14") (pin "2") (pinfunction "2_2") (pintype "passive"))
      (node (ref "C15") (pin "2") (pinfunction "2_2") (pintype "passive"))
      (node (ref "C16") (pin "2") (pinfunction "2_2") (pintype "passive"))
      (node (ref "C17") (pin "2") (pinfunction "2_2") (pintype "passive"))
      (node (ref "C19") (pin "2") (pinfunction "2_2") (pintype "passive"))
      (node (ref "C2") (pin "2") (pinfunction "2_2") (pintype "passive"))
      (node (ref "C20") (pin "2") (pinfunction "2_2") (pintype "passive"))
      (node (ref "C21") (pin "2") (pinfunction "2_2") (pintype "passive"))
      (node (ref "C22") (pin "2") (pinfunction "2_2") (pintype "passive"))
      (node (ref "C23") (pin "2") (pinfunction "2_2") (pintype "passive"))
      (node (ref "C24") (pin "2") (pinfunction "2_2") (pintype "passive"))
      (node (ref "C25") (pin "1") (pinfunction "1_1") (pintype "passive"))
      (node (ref "C26") (pin "2") (pinfunction "2_2") (pintype "passive"))
      (node (ref "C27") (pin "1") (pinfunction "1_1") (pintype "passive"))
      (node (ref "C28") (pin "2") (pinfunction "2_2") (pintype "passive"))
      (node (ref "C29") (pin "2") (pinfunction "2_2") (pintype "passive"))
      (node (ref "C3") (pin "2") (pinfunction "2_2") (pintype "passive"))
      (node (ref "C30") (pin "2") (pinfunction "2_2") (pintype "passive"))
      (node (ref "C31") (pin "2") (pinfunction "2_2") (pintype "passive"))
      (node (ref "C32") (pin "2") (pinfunction "2_2") (pintype "passive"))
      (node (ref "C33") (pin "2") (pinfunction "2_2") (pintype "passive"))
      (node (ref "C34") (pin "2") (pinfunction "2_2") (pintype "passive"))
      (node (ref "C4") (pin "2") (pinfunction "2_2") (pintype "passive"))
      (node (ref "C5") (pin "2") (pinfunction "2_2") (pintype "passive"))
      (node (ref "C6") (pin "2") (pinfunction "2_2") (pintype "passive"))
      (node (ref "C7") (pin "1") (pinfunction "1_1") (pintype "passive"))
      (node (ref "C8") (pin "2") (pinfunction "2_2") (pintype "passive"))
      (node (ref "C9") (pin "1") (pinfunction "1_1") (pintype "passive"))
      (node (ref "D1") (pin "1") (pinfunction "cathode_1") (pintype "passive"))
      (node (ref "J1") (pin "6") (pinfunction "6_6") (pintype "passive"))
      (node (ref "J1") (pin "7") (pinfunction "7_7") (pintype "passive"))
      (node (ref "J4") (pin "7") (pinfunction "7_7") (pintype "passive"))
      (node (ref "J5") (pin "6") (pinfunction "6_6") (pintype "passive"))
      (node (ref "J6") (pin "6") (pinfunction "6_6") (pintype "passive"))
      (node (ref "J7") (pin "10") (pinfunction "10_10") (pintype "passive"))
      (node (ref "J7") (pin "11") (pinfunction "11_11") (pintype "passive"))
      (node (ref "J7") (pin "5") (pinfunction "P5_5") (pintype "passive"))
      (node (ref "J7") (pin "6") (pinfunction "6_6") (pintype "passive"))
      (node (ref "J7") (pin "7") (pinfunction "7_7") (pintype "passive"))
      (node (ref "J7") (pin "8") (pinfunction "8_8") (pintype "passive"))
      (node (ref "J7") (pin "9") (pinfunction "9_9") (pintype "passive"))
      (node (ref "J9") (pin "1") (pinfunction "1_1") (pintype "passive"))
      (node (ref "MH1") (pin "1") (pinfunction "1_1") (pintype "passive"))
      (node (ref "MH2") (pin "1") (pinfunction "1_1") (pintype "passive"))
      (node (ref "MH3") (pin "1") (pinfunction "1_1") (pintype "passive"))
      (node (ref "R12") (pin "2") (pinfunction "2_2") (pintype "passive"))
      (node (ref "R8") (pin "2") (pinfunction "2_2") (pintype "passive"))
      (node (ref "SW1") (pin "3") (pinfunction "MECH1_3") (pintype "passive"))
      (node (ref "SW1") (pin "4") (pinfunction "MECH2_4") (pintype "passive"))
      (node (ref "SW2") (pin "3") (pinfunction "MECH1_3") (pintype "passive"))
      (node (ref "SW2") (pin "4") (pinfunction "MECH2_4") (pintype "passive"))
      (node (ref "U1") (pin "22") (pinfunction "GND_2_22") (pintype "passive"))
      (node (ref "U1") (pin "8") (pinfunction "GND_1_8") (pintype "passive"))
      (node (ref "U2") (pin "28") (pinfunction "UGND_28") (pintype "passive"))
      (node (ref "U2") (pin "3") (pinfunction "GND_3") (pintype "passive"))
      (node (ref "U3") (pin "3") (pinfunction "GND_3") (pintype "passive"))
      (node (ref "U3") (pin "6") (pinfunction "EPAD_6") (pintype "passive"))
      (node (ref "U4") (pin "3") (pinfunction "GND_3") (pintype "power_in"))
      (node (ref "U5") (pin "3") (pinfunction "GND_3") (pintype "power_in"))
      (node (ref "U6") (pin "3") (pinfunction "GND_3") (pintype "power_in"))
      (node (ref "U7") (pin "3") (pinfunction "GND_3") (pintype "power_in"))
      (node (ref "Z1") (pin "1") (pinfunction "1_1") (pintype "passive"))
      (node (ref "Z2") (pin "1") (pinfunction "1_1") (pintype "passive"))
    )
    (net (code "62") (name "Net-(C11-Pad2)") (class "Default")
      (node (ref "C11") (pin "2") (pinfunction "2_2") (pintype "passive"))
      (node (ref "JP1") (pin "1") (pinfunction "1_1") (pintype "passive"))
    )
    (net (code "63") (name "Net-(D1-ANODE)") (class "Default")
      (node (ref "D1") (pin "2") (pinfunction "ANODE_2") (pintype "passive"))
      (node (ref "R17") (pin "1") (pinfunction "1_1") (pintype "passive"))
    )
    (net (code "64") (name "Net-(D2-ANODE)") (class "Default")
      (node (ref "D2") (pin "2") (pinfunction "ANODE_2") (pintype "passive"))
      (node (ref "R15") (pin "1") (pinfunction "1_1") (pintype "passive"))
    )
    (net (code "65") (name "Net-(D2-cathode)") (class "Default")
      (node (ref "D2") (pin "1") (pinfunction "cathode_1") (pintype "passive"))
      (node (ref "U4") (pin "4") (pinfunction "Y_4") (pintype "passive"))
    )
    (net (code "66") (name "Net-(D3-ANODE)") (class "Default")
      (node (ref "D3") (pin "2") (pinfunction "ANODE_2") (pintype "passive"))
      (node (ref "R2") (pin "1") (pinfunction "1_1") (pintype "passive"))
    )
    (net (code "67") (name "Net-(D4-ANODE)") (class "Default")
      (node (ref "D4") (pin "2") (pinfunction "ANODE_2") (pintype "passive"))
      (node (ref "R3") (pin "1") (pinfunction "1_1") (pintype "passive"))
    )
    (net (code "68") (name "Net-(D5-Anode)") (class "Default")
      (node (ref "D5") (pin "2") (pinfunction "Anode_2") (pintype "passive"))
      (node (ref "R19") (pin "1") (pinfunction "1_1") (pintype "passive"))
      (node (ref "R23") (pin "1") (pinfunction "1_1") (pintype "passive"))
    )
    (net (code "69") (name "Net-(J7-P4)") (class "Default")
      (node (ref "J7") (pin "4") (pinfunction "P4_4") (pintype "passive"))
      (node (ref "R8") (pin "1") (pinfunction "1_1") (pintype "passive"))
    )
    (net (code "70") (name "Net-(JP1-Pad3)") (class "Default")
      (node (ref "JP1") (pin "3") (pinfunction "3_3") (pintype "passive"))
      (node (ref "R12") (pin "1") (pinfunction "1_1") (pintype "passive"))
    )
    (net (code "71") (name "Net-(U7-Y)") (class "Default")
      (node (ref "R22") (pin "2") (pinfunction "2_2") (pintype "passive"))
      (node (ref "U7") (pin "4") (pinfunction "Y_4") (pintype "passive"))
    )
    (net (code "72") (name "unconnected-(J1-Pad1)") (class "Default")
      (node (ref "J1") (pin "1") (pinfunction "1_1") (pintype "passive+no_connect"))
    )
    (net (code "73") (name "unconnected-(J1-Pad8)") (class "Default")
      (node (ref "J1") (pin "8") (pinfunction "8_8") (pintype "passive+no_connect"))
    )
    (net (code "74") (name "unconnected-(MH4-Pad1)") (class "Default")
      (node (ref "MH4") (pin "1") (pinfunction "1_1") (pintype "passive+no_connect"))
    )
    (net (code "75") (name "unconnected-(U2-AIN0_{slash}_INT1_{slash}_PD1-Pad7)") (class "Default")
      (node (ref "U2") (pin "7") (pinfunction "AIN0_/_INT1_/_PD1_7") (pintype "passive+no_connect"))
    )
    (net (code "76") (name "unconnected-(U2-AIN2_{slash}_PCINT11_{slash}_PC2-Pad5)") (class "Default")
      (node (ref "U2") (pin "5") (pinfunction "AIN2_/_PCINT11_/_PC2_5") (pintype "passive+no_connect"))
    )
    (net (code "77") (name "unconnected-(U2-CLKO_{slash}_ICP1_{slash}_INT4_{slash}_PC7-Pad22)") (class "Default")
      (node (ref "U2") (pin "22") (pinfunction "CLKO_/_ICP1_/_INT4_/_PC7_22") (pintype "passive+no_connect"))
    )
    (net (code "78") (name "unconnected-(U2-OC.0B_{slash}_INT0_{slash}_PD0-Pad6)") (class "Default")
      (node (ref "U2") (pin "6") (pinfunction "OC.0B_/_INT0_/_PD0_6") (pintype "passive+no_connect"))
    )
    (net (code "79") (name "unconnected-(U2-OC.1A_{slash}_PCINT8_{slash}_PC6-Pad23)") (class "Default")
      (node (ref "U2") (pin "23") (pinfunction "OC.1A_/_PCINT8_/_PC6_23") (pintype "passive+no_connect"))
    )
    (net (code "80") (name "unconnected-(U2-OC.1B_{slash}_PCINT9_{slash}_PC5-Pad25)") (class "Default")
      (node (ref "U2") (pin "25") (pinfunction "OC.1B_/_PCINT9_/_PC5_25") (pintype "passive+no_connect"))
    )
    (net (code "81") (name "unconnected-(U2-PCINT10_{slash}_PC4-Pad26)") (class "Default")
      (node (ref "U2") (pin "26") (pinfunction "PCINT10_/_PC4_26") (pintype "passive+no_connect"))
    )
    (net (code "82") (name "unconnected-(U2-~{RTS}_{slash}_AIN5_{slash}_INT6_{slash}_PD6-Pad12)") (class "Default")
      (node (ref "U2") (pin "12") (pinfunction "~{RTS}_/_AIN5_/_INT6_/_PD6_12") (pintype "passive"))
    )
    (net (code "83") (name "unconnected-(U2-~{SS}_{slash}_PCINT0_{slash}_PB0-Pad14)") (class "Default")
      (node (ref "U2") (pin "14") (pinfunction "~{SS}_/_PCINT0_/_PB0_14") (pintype "passive+no_connect"))
    )
    (net (code "84") (name "unconnected-(U3-IN-Pad2)") (class "Default")
      (node (ref "U3") (pin "2") (pinfunction "IN_2") (pintype "passive"))
    )
    (net (code "85") (name "unconnected-(U3-~{SHDN}-Pad1)") (class "Default")
      (node (ref "U3") (pin "1") (pinfunction "~{SHDN}_1") (pintype "passive"))
    )
  )
)
